# Attenuverting_LinExp_VCA-alt1.net
KiCad netlist of a schematic drawn in EAGLE
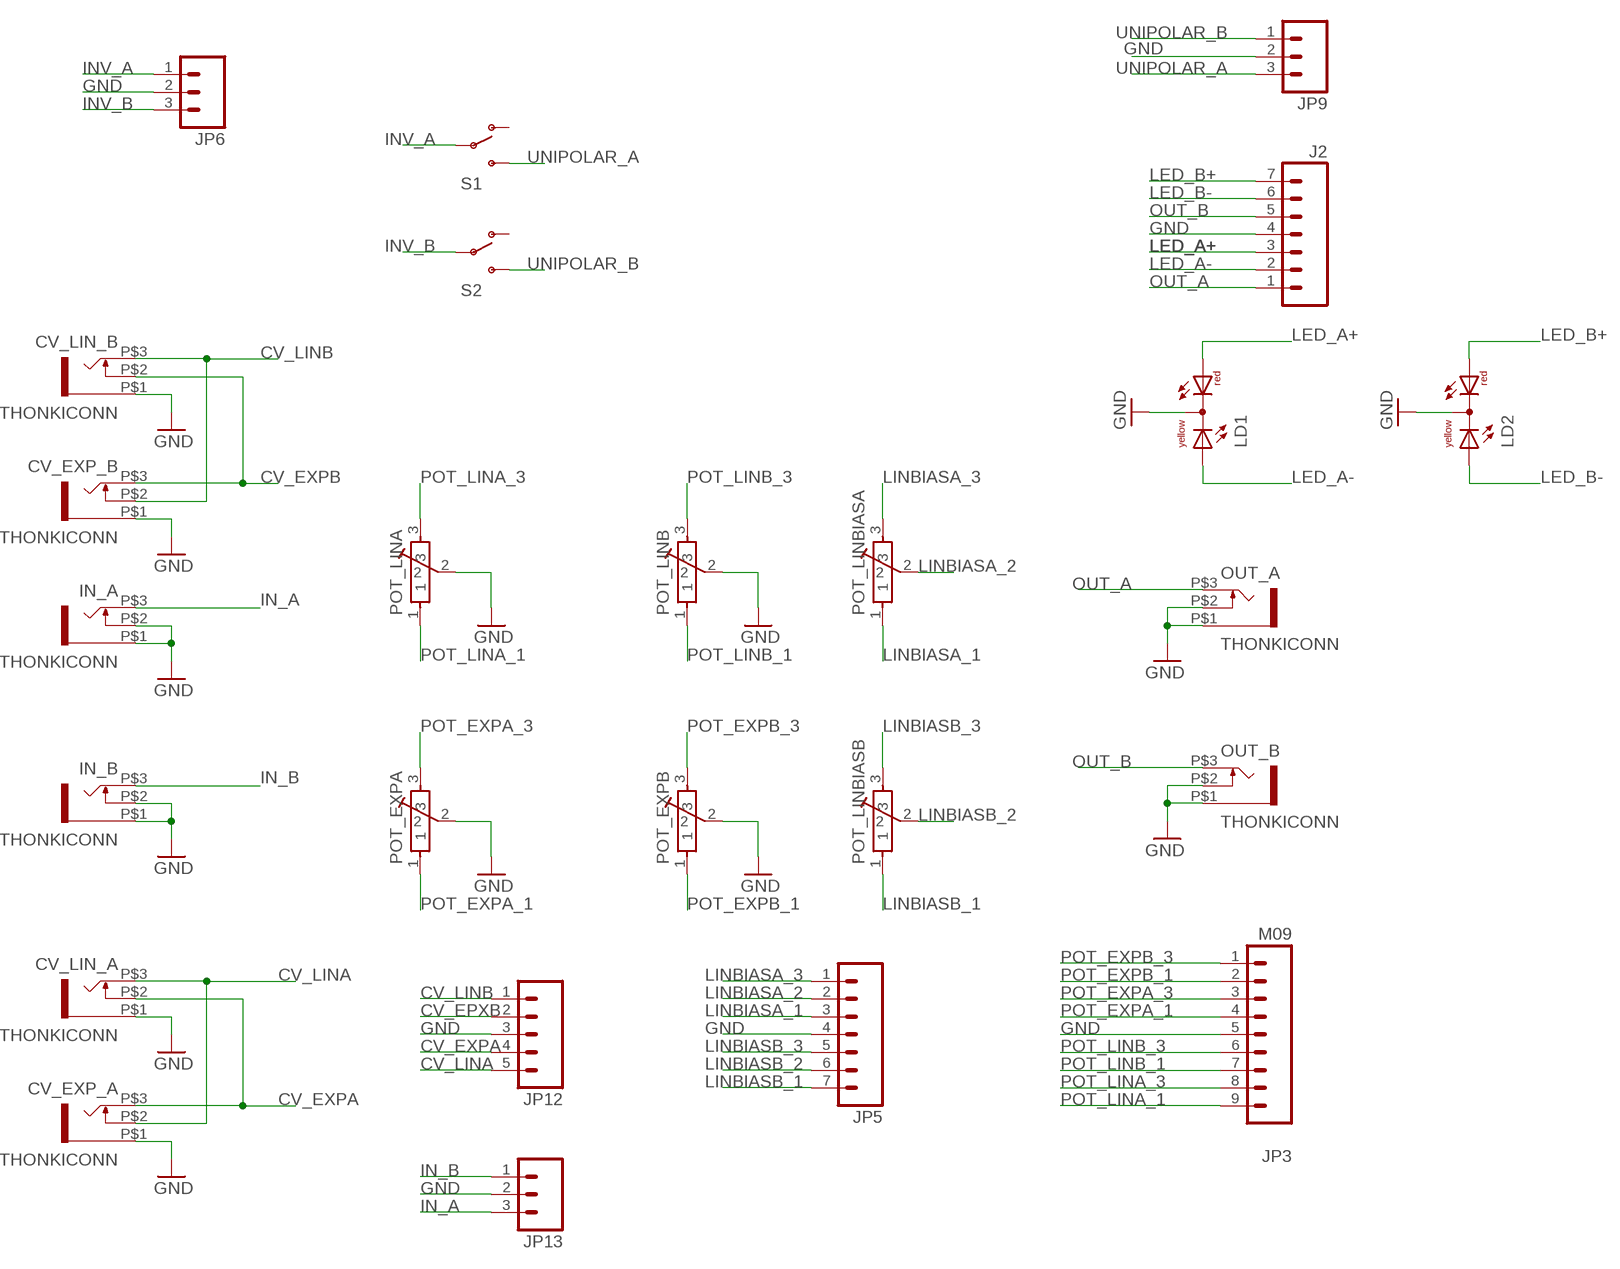
[diagram p0: schematic, sheet 1]
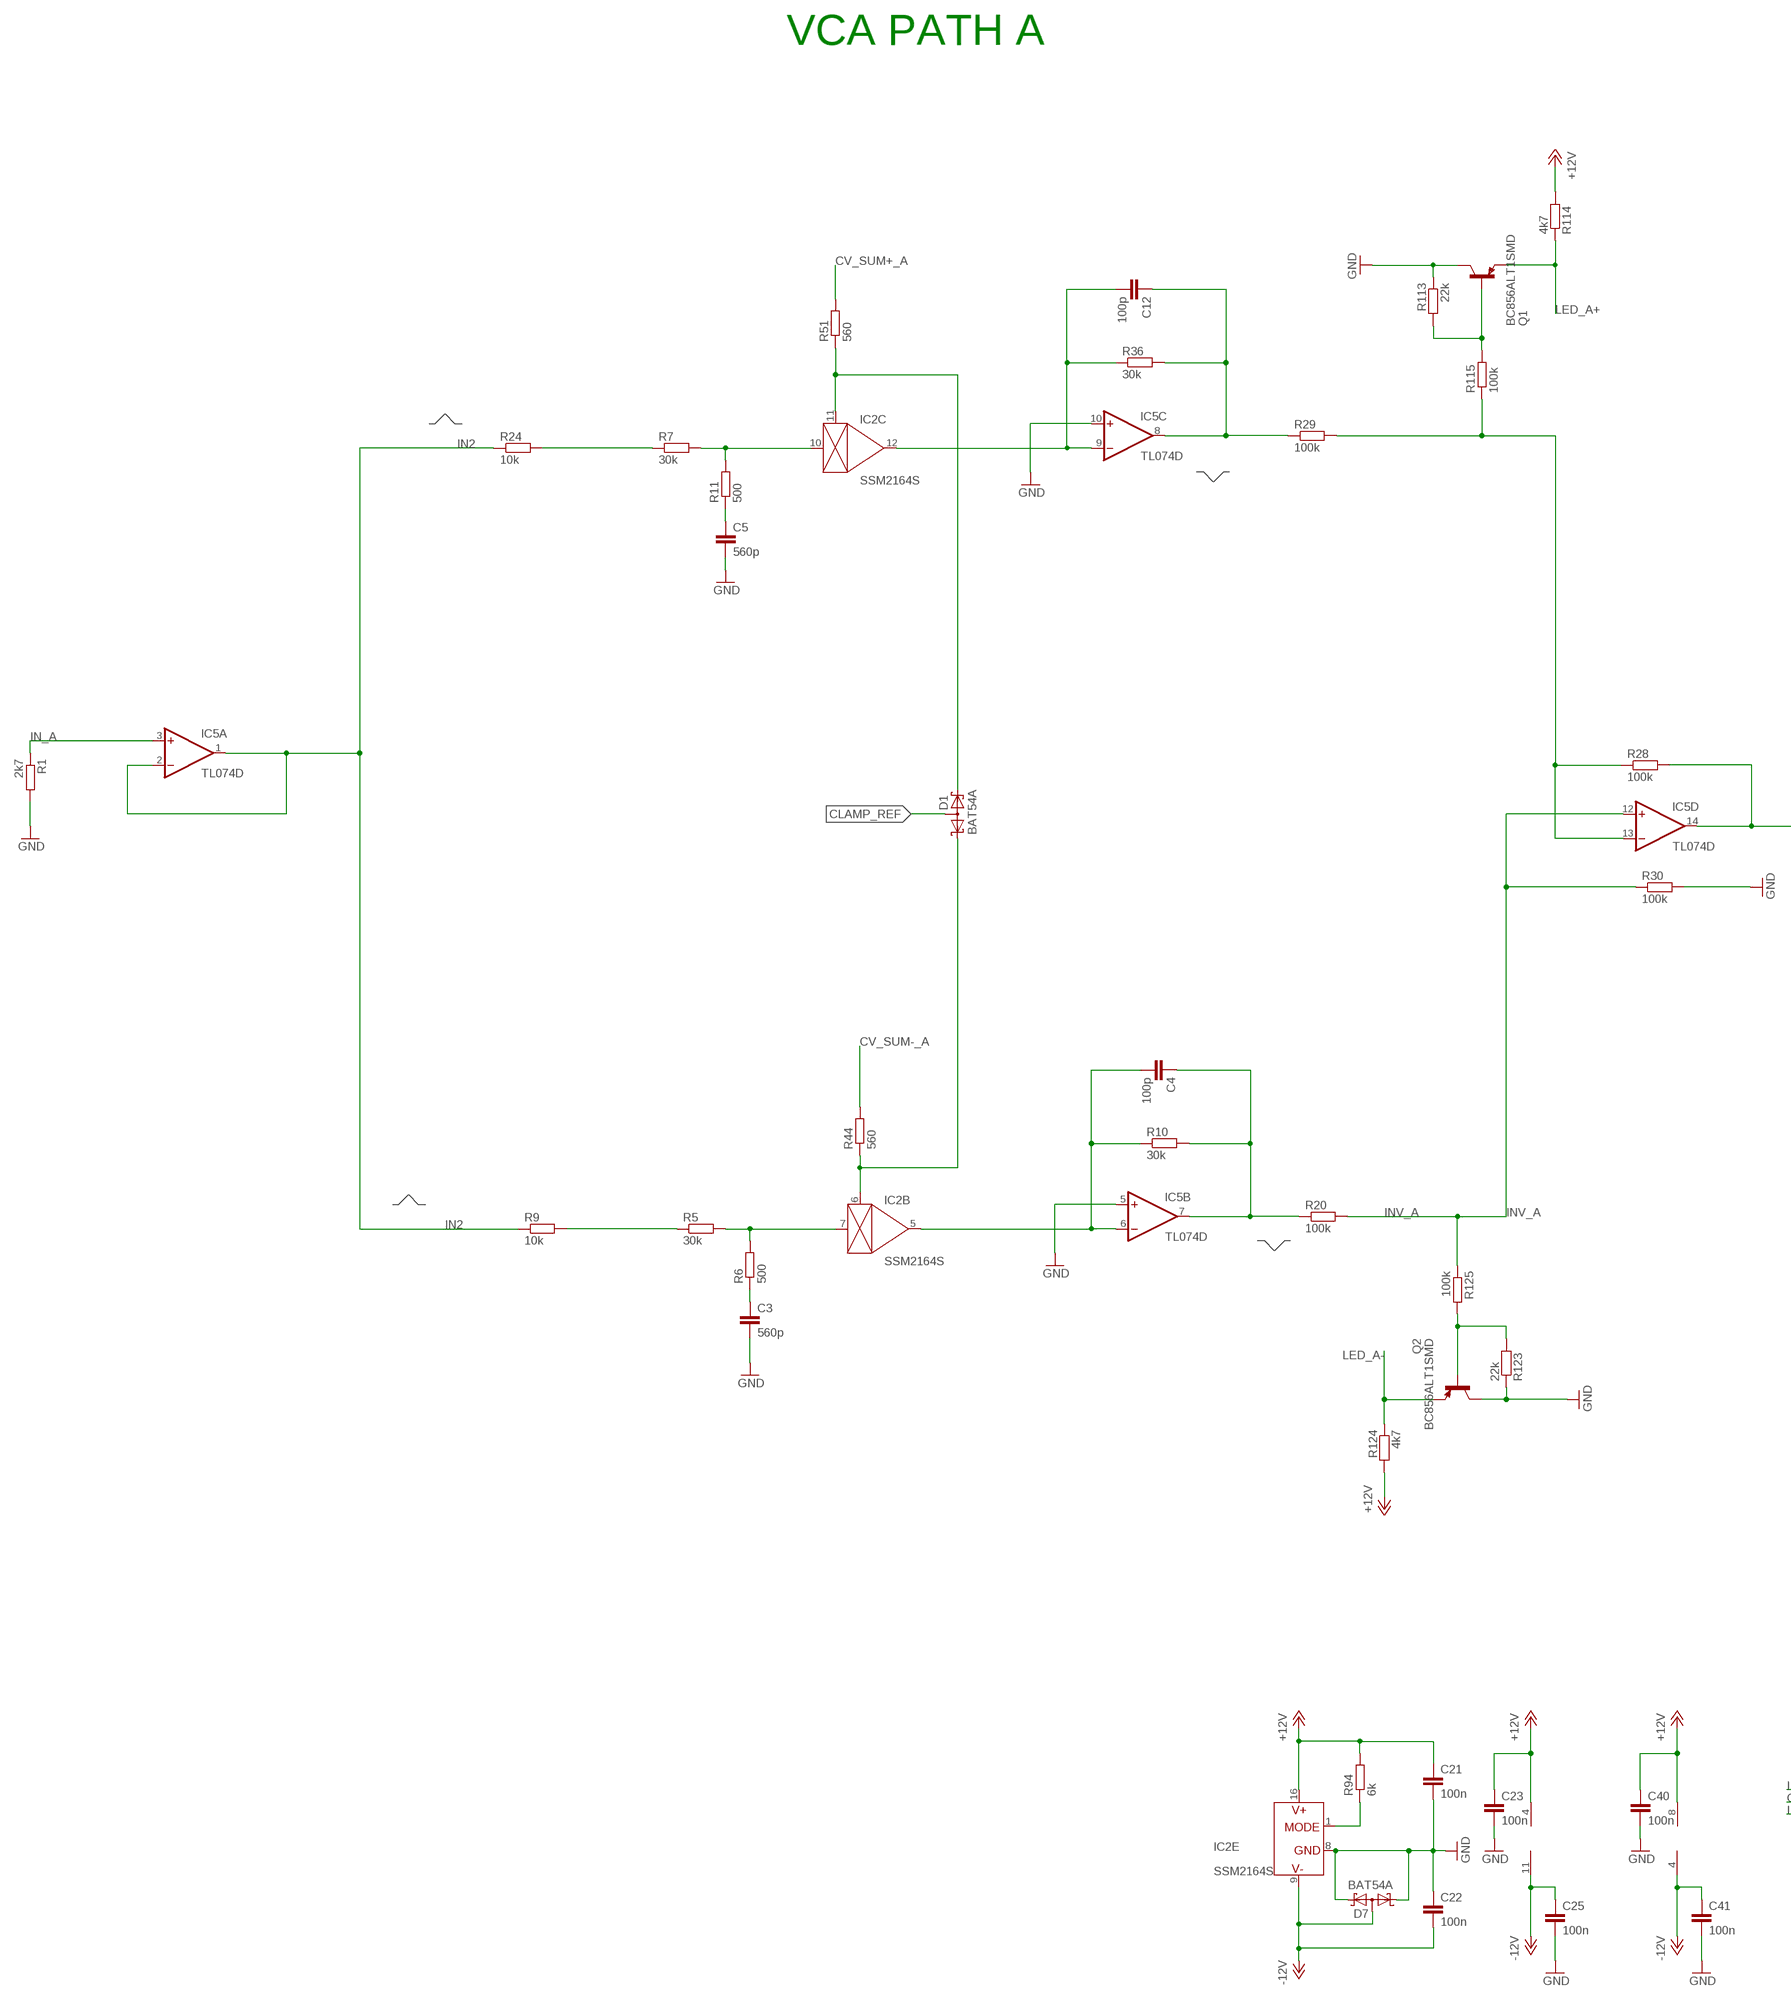
[diagram p1: schematic, sheet 2, part 1 of 2]
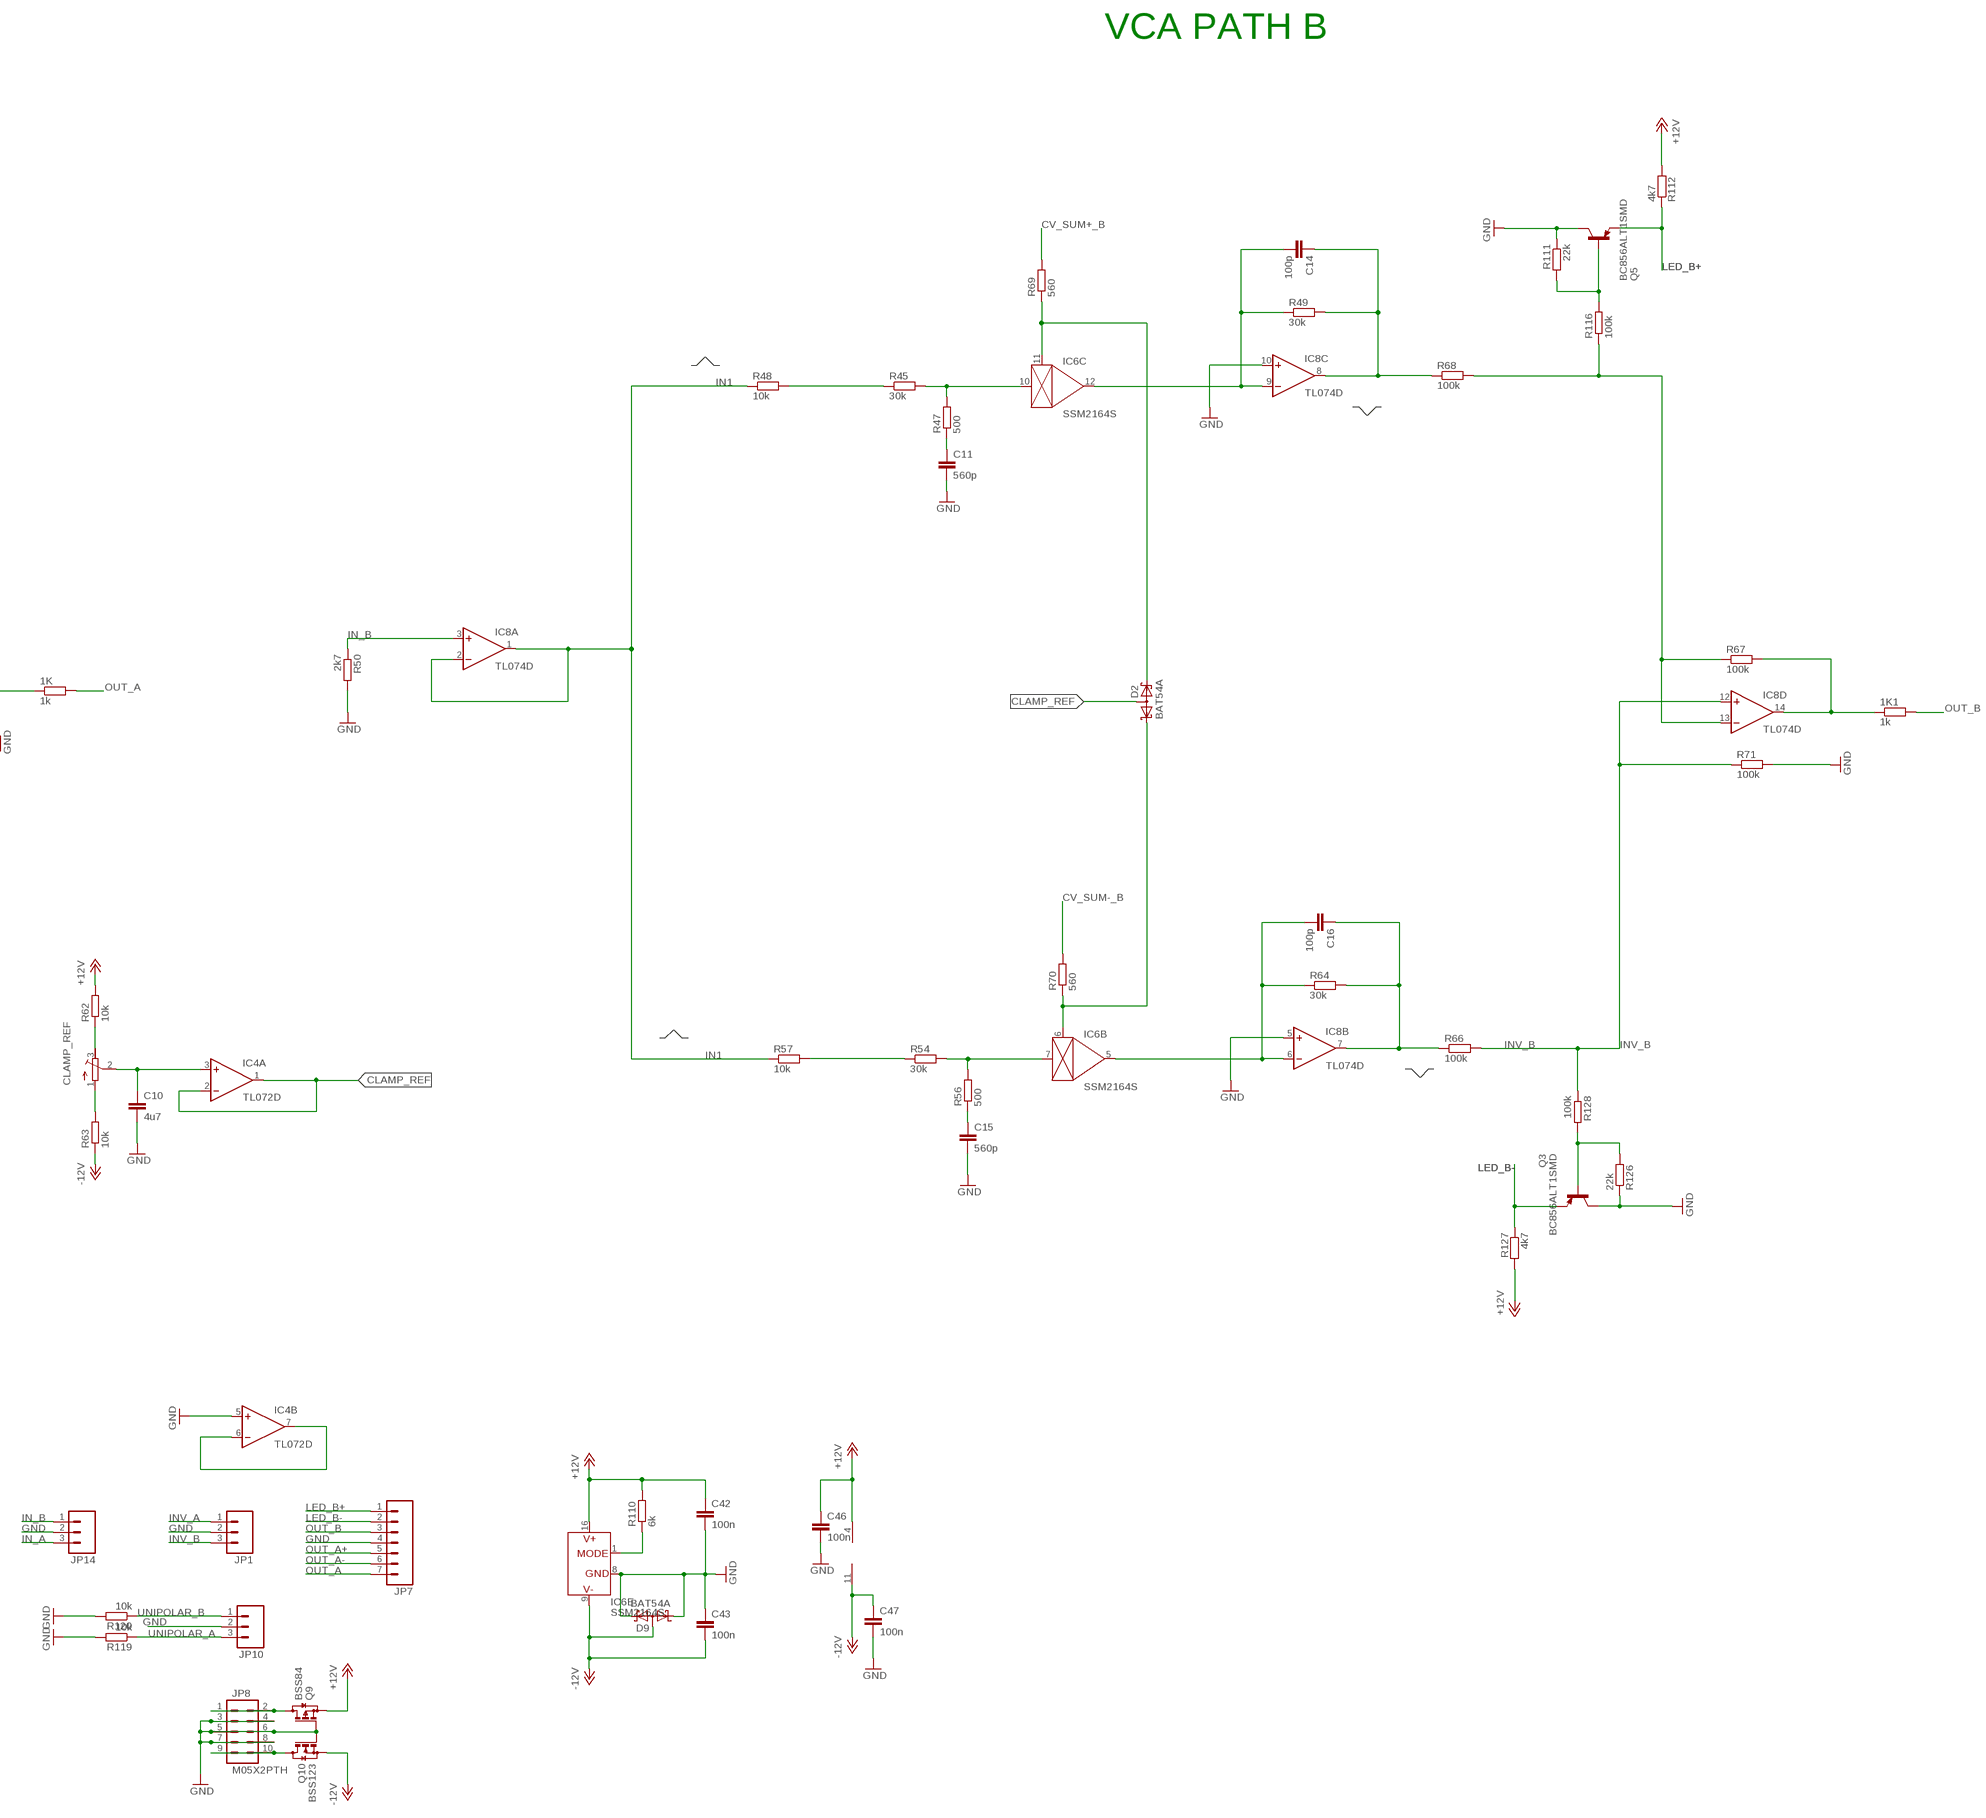
[diagram p2: schematic, sheet 2, part 2 of 2]
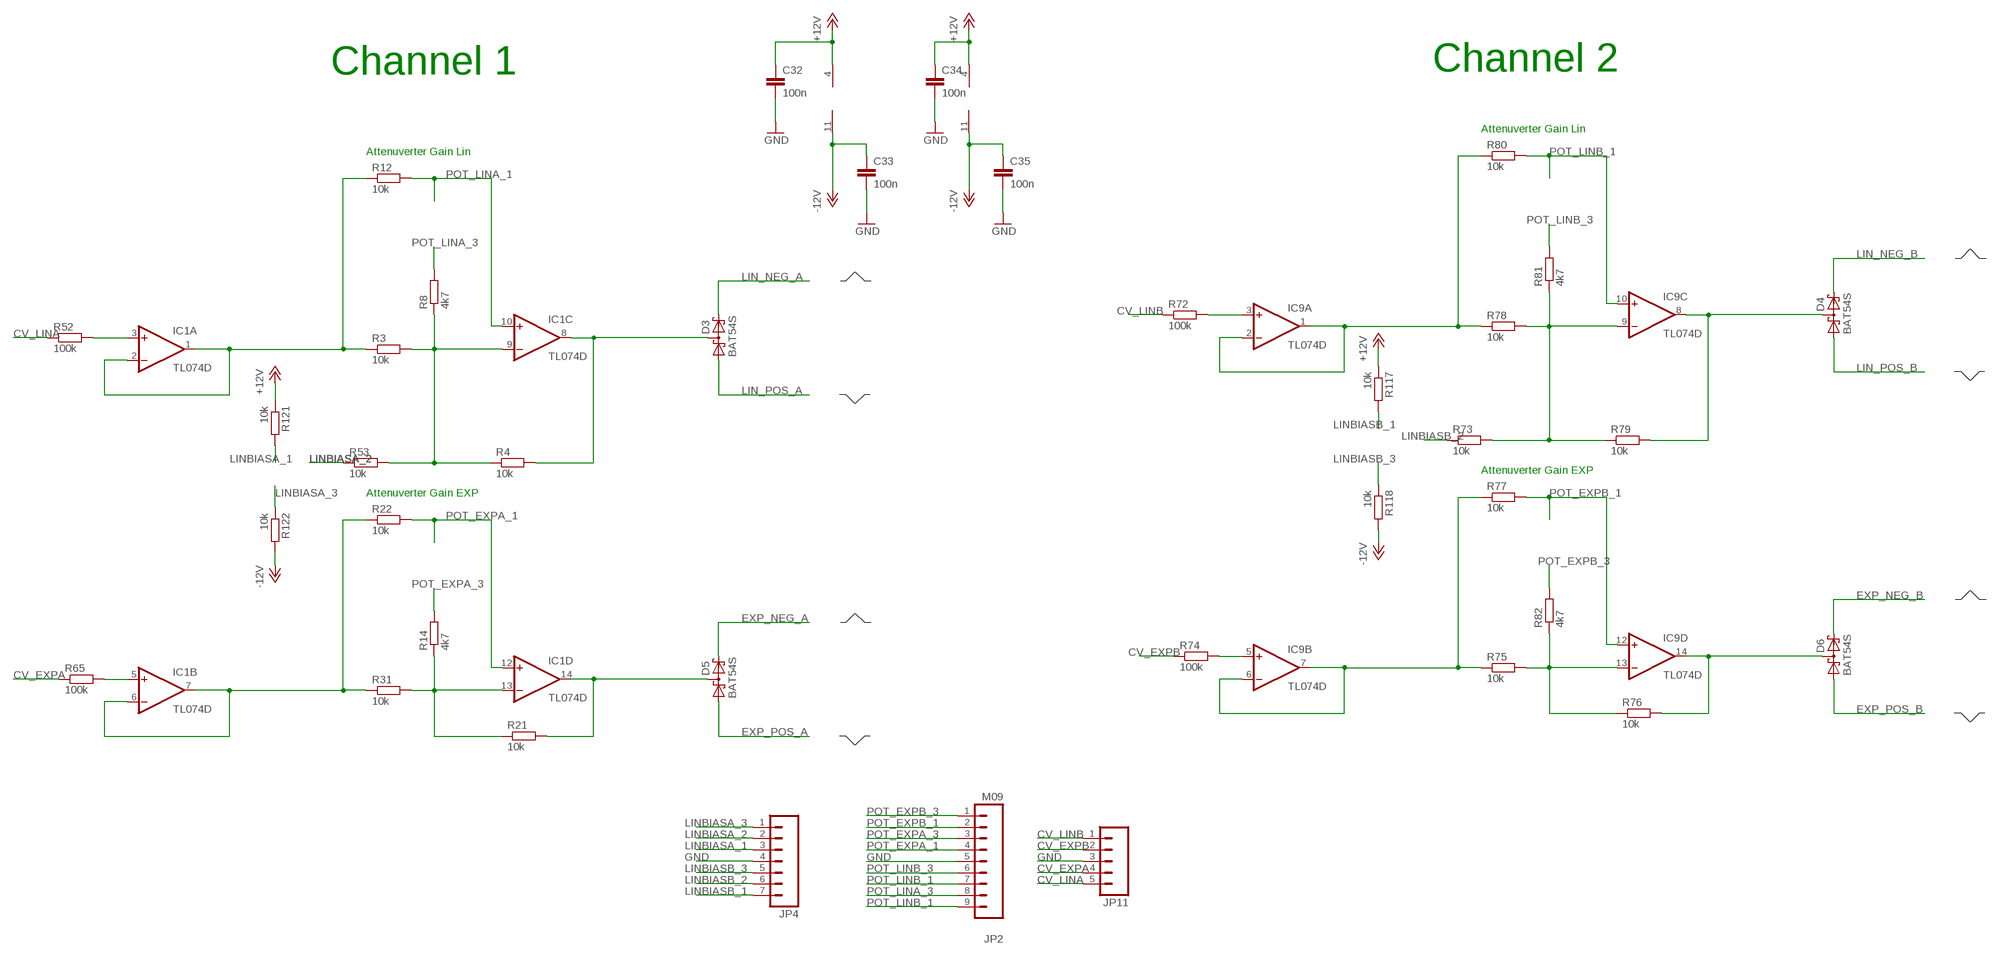
[diagram p3: schematic, sheet 3]
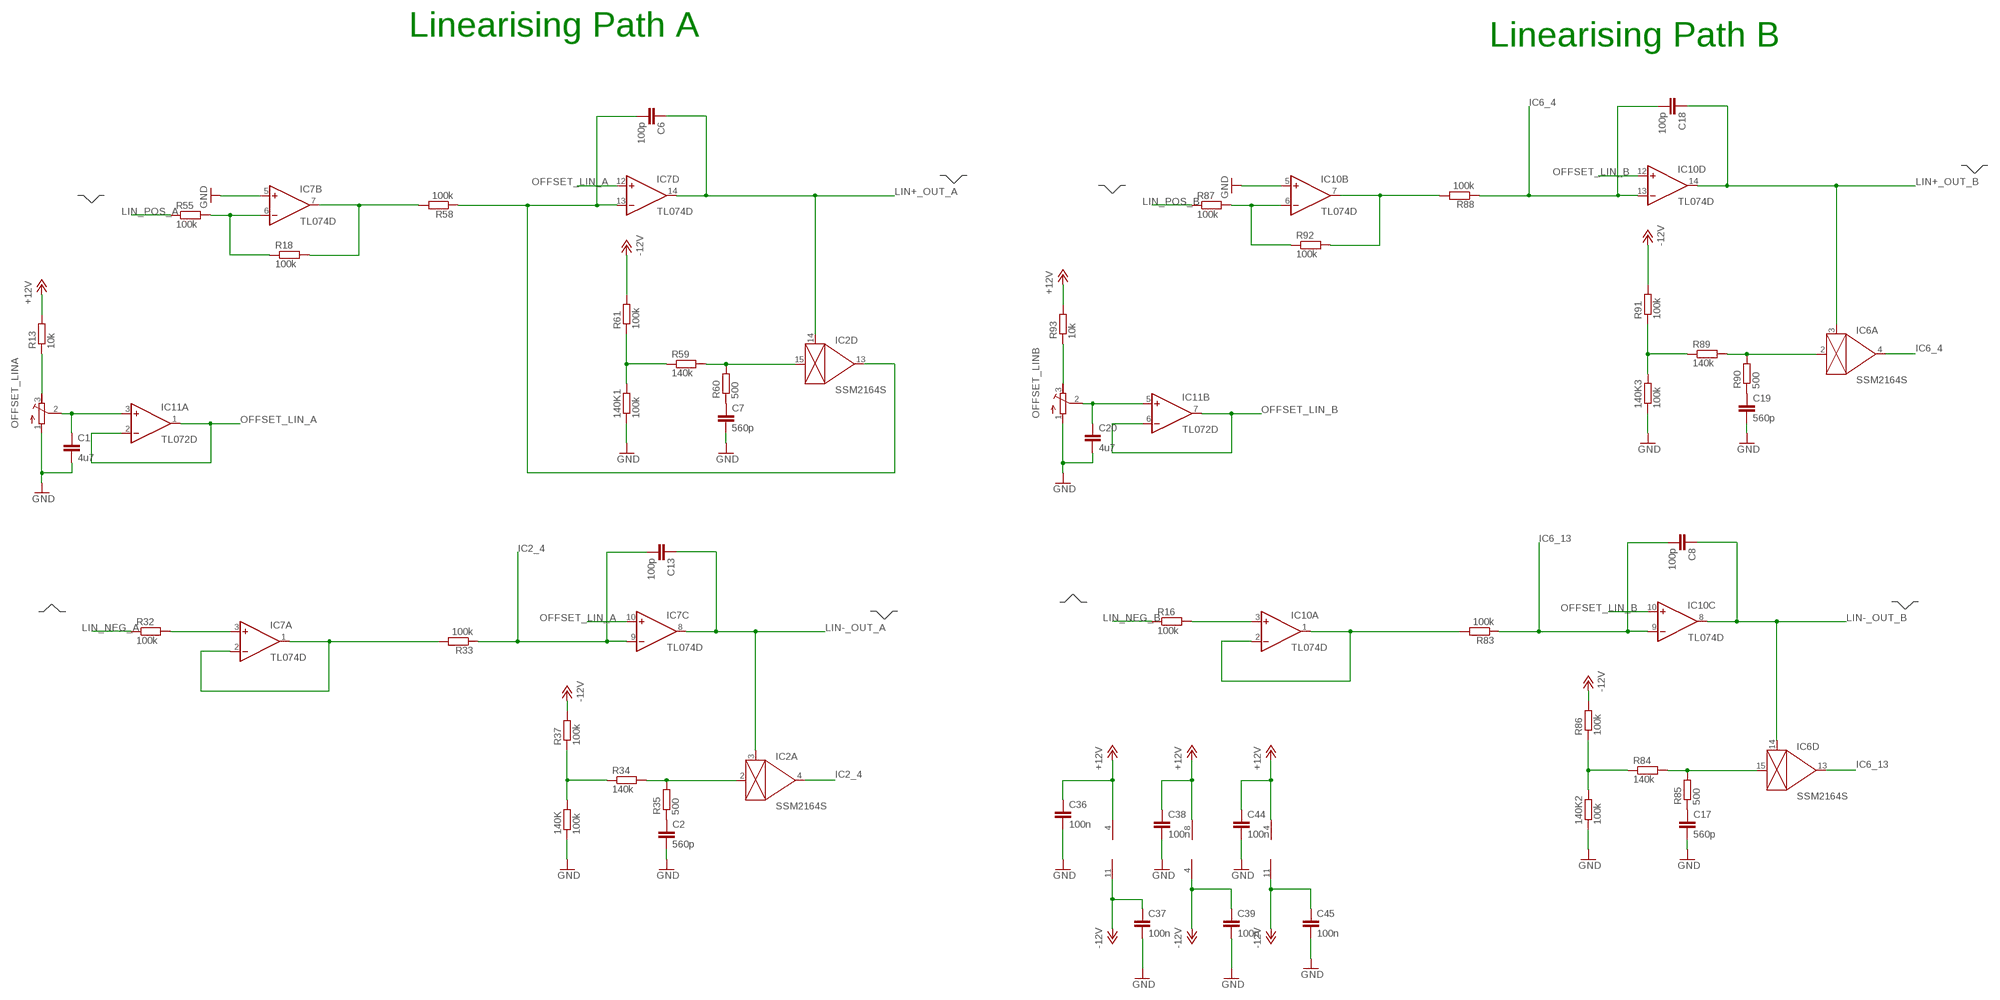
[diagram p4: schematic, sheet 4]
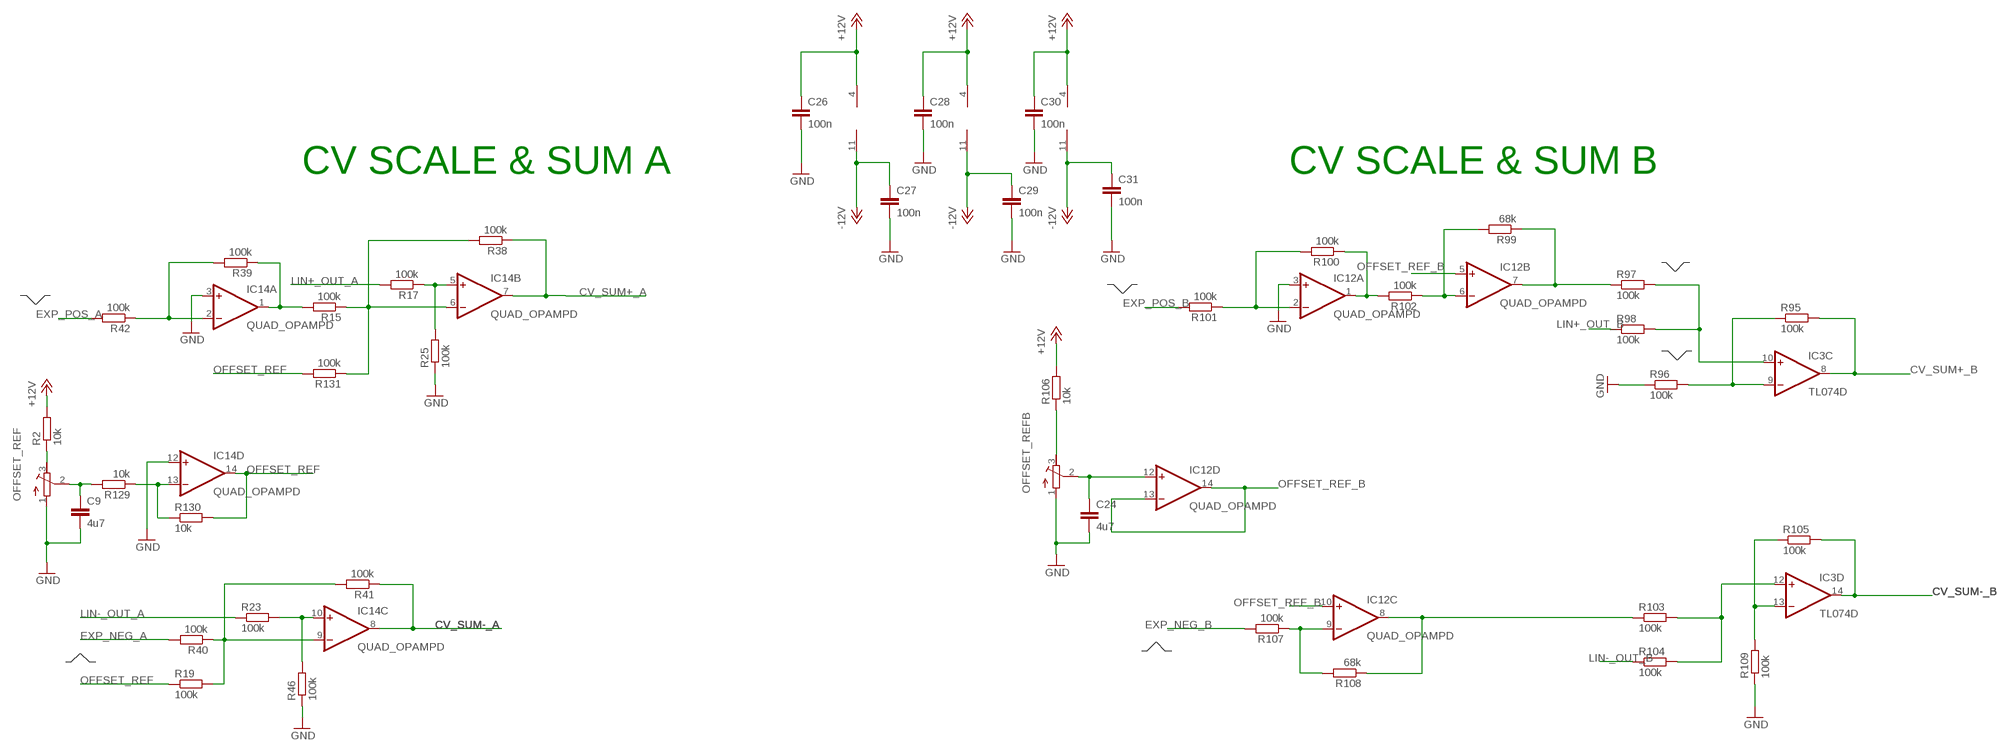
[diagram p5: schematic, sheet 5]

(export (version "E")
  (design (tool "Eeschema 10.0.6"))
  (components
    (comp (ref "1K")
      (value "1k")
      (footprint "eagle-import:0603")
      (fields (field (name "MF") "MULTICOMP") (field (name "MPN") "MC0063W06031160K"))
      (libsource (lib "eagle-import") (part "R-EU_0603"))
    )
    (comp (ref "1K1")
      (value "1k")
      (footprint "eagle-import:0603")
      (fields (field (name "MF") "MULTICOMP") (field (name "MPN") "MC0063W06031160K"))
      (libsource (lib "eagle-import") (part "R-EU_0603"))
    )
    (comp (ref "C3")
      (value "560p")
      (footprint "eagle-import:C0603K")
      (libsource (lib "eagle-import") (part "resistor_C-EUC0603K"))
    )
    (comp (ref "C4")
      (value "100p")
      (footprint "eagle-import:C0603K")
      (libsource (lib "eagle-import") (part "resistor_C-EUC0603K"))
    )
    (comp (ref "C5")
      (value "560p")
      (footprint "eagle-import:C0603K")
      (libsource (lib "eagle-import") (part "resistor_C-EUC0603K"))
    )
    (comp (ref "C10")
      (value "4u7")
      (footprint "eagle-import:C0603K")
      (libsource (lib "eagle-import") (part "resistor_C-EUC0603K"))
    )
    (comp (ref "C11")
      (value "560p")
      (footprint "eagle-import:C0603K")
      (libsource (lib "eagle-import") (part "resistor_C-EUC0603K"))
    )
    (comp (ref "C12")
      (value "100p")
      (footprint "eagle-import:C0603K")
      (libsource (lib "eagle-import") (part "resistor_C-EUC0603K"))
    )
    (comp (ref "C14")
      (value "100p")
      (footprint "eagle-import:C0603K")
      (libsource (lib "eagle-import") (part "resistor_C-EUC0603K"))
    )
    (comp (ref "C15")
      (value "560p")
      (footprint "eagle-import:C0603K")
      (libsource (lib "eagle-import") (part "resistor_C-EUC0603K"))
    )
    (comp (ref "C16")
      (value "100p")
      (footprint "eagle-import:C0603K")
      (libsource (lib "eagle-import") (part "resistor_C-EUC0603K"))
    )
    (comp (ref "C21")
      (value "100n")
      (footprint "eagle-import:C0603K")
      (libsource (lib "eagle-import") (part "C-EUC0603K"))
    )
    (comp (ref "C22")
      (value "100n")
      (footprint "eagle-import:C0603K")
      (libsource (lib "eagle-import") (part "C-EUC0603K"))
    )
    (comp (ref "C23")
      (value "100n")
      (footprint "eagle-import:C0603K")
      (libsource (lib "eagle-import") (part "C-EUC0603K"))
    )
    (comp (ref "C25")
      (value "100n")
      (footprint "eagle-import:C0603K")
      (libsource (lib "eagle-import") (part "C-EUC0603K"))
    )
    (comp (ref "C40")
      (value "100n")
      (footprint "eagle-import:C0603K")
      (libsource (lib "eagle-import") (part "C-EUC0603K"))
    )
    (comp (ref "C41")
      (value "100n")
      (footprint "eagle-import:C0603K")
      (libsource (lib "eagle-import") (part "C-EUC0603K"))
    )
    (comp (ref "C42")
      (value "100n")
      (footprint "eagle-import:C0603K")
      (libsource (lib "eagle-import") (part "C-EUC0603K"))
    )
    (comp (ref "C43")
      (value "100n")
      (footprint "eagle-import:C0603K")
      (libsource (lib "eagle-import") (part "C-EUC0603K"))
    )
    (comp (ref "C46")
      (value "100n")
      (footprint "eagle-import:C0603K")
      (libsource (lib "eagle-import") (part "C-EUC0603K"))
    )
    (comp (ref "C47")
      (value "100n")
      (footprint "eagle-import:C0603K")
      (libsource (lib "eagle-import") (part "C-EUC0603K"))
    )
    (comp (ref "CLAMP_REF")
      (value "R-TRIMM64W")
      (footprint "eagle-import:RTRIM64W")
      (libsource (lib "eagle-import") (part "R-TRIMM64W"))
    )
    (comp (ref "D1")
      (value "BAT54A")
      (footprint "eagle-import:SOT23")
      (libsource (lib "eagle-import") (part "BAT54A"))
    )
    (comp (ref "D2")
      (value "BAT54A")
      (footprint "eagle-import:SOT23")
      (libsource (lib "eagle-import") (part "BAT54A"))
    )
    (comp (ref "D7")
      (value "BAT54A")
      (footprint "eagle-import:SOT23")
      (libsource (lib "eagle-import") (part "BAT54A"))
    )
    (comp (ref "D9")
      (value "BAT54A")
      (footprint "eagle-import:SOT23")
      (libsource (lib "eagle-import") (part "BAT54A"))
    )
    (comp (ref "IC2")
      (value "SSM2164S")
      (footprint "eagle-import:SOIC16N")
      (fields (field (name "OC_FARNELL") "unknown"))
      (libsource (lib "eagle-import") (part "SSM2164S"))
    )
    (comp (ref "IC4")
      (value "TL072D")
      (footprint "eagle-import:SO08")
      (libsource (lib "eagle-import") (part "TL072D"))
    )
    (comp (ref "IC5")
      (value "TL074D")
      (footprint "eagle-import:SO14")
      (fields (field (name "OC_FARNELL") "unknown"))
      (libsource (lib "eagle-import") (part "TL074D"))
    )
    (comp (ref "IC6")
      (value "SSM2164S")
      (footprint "eagle-import:SOIC16N")
      (fields (field (name "OC_FARNELL") "unknown"))
      (libsource (lib "eagle-import") (part "SSM2164S"))
    )
    (comp (ref "IC8")
      (value "TL074D")
      (footprint "eagle-import:SO14")
      (fields (field (name "OC_FARNELL") "unknown"))
      (libsource (lib "eagle-import") (part "TL074D"))
    )
    (comp (ref "JP1")
      (value "M03PTH")
      (footprint "eagle-import:1X03")
      (libsource (lib "eagle-import") (part "M03PTH"))
    )
    (comp (ref "JP7")
      (value "M07")
      (footprint "eagle-import:1X07")
      (libsource (lib "eagle-import") (part "M07"))
    )
    (comp (ref "JP8")
      (value "M05X2PTH")
      (footprint "eagle-import:AVR_ICSP")
      (libsource (lib "eagle-import") (part "M05X2PTH"))
    )
    (comp (ref "JP10")
      (value "M03PTH")
      (footprint "eagle-import:1X03")
      (libsource (lib "eagle-import") (part "M03PTH"))
    )
    (comp (ref "JP14")
      (value "M03PTH")
      (footprint "eagle-import:1X03")
      (libsource (lib "eagle-import") (part "M03PTH"))
    )
    (comp (ref "Q1")
      (value "BC856ALT1SMD")
      (footprint "eagle-import:SOT23-BEC")
      (libsource (lib "eagle-import") (part "BC856SMDALT1"))
    )
    (comp (ref "Q2")
      (value "BC856ALT1SMD")
      (footprint "eagle-import:SOT23-BEC")
      (libsource (lib "eagle-import") (part "BC856SMDALT1"))
    )
    (comp (ref "Q3")
      (value "BC856ALT1SMD")
      (footprint "eagle-import:SOT23-BEC")
      (libsource (lib "eagle-import") (part "BC856SMDALT1"))
    )
    (comp (ref "Q5")
      (value "BC856ALT1SMD")
      (footprint "eagle-import:SOT23-BEC")
      (libsource (lib "eagle-import") (part "BC856SMDALT1"))
    )
    (comp (ref "Q9")
      (value "BSS84")
      (footprint "eagle-import:SOT23")
      (libsource (lib "eagle-import") (part "BSS84"))
    )
    (comp (ref "Q10")
      (value "BSS123")
      (footprint "eagle-import:SOT23")
      (libsource (lib "eagle-import") (part "BSS123"))
    )
    (comp (ref "R1")
      (value "2k7")
      (footprint "eagle-import:0603")
      (libsource (lib "eagle-import") (part "R-EU_0603"))
    )
    (comp (ref "R5")
      (value "30k")
      (footprint "eagle-import:0603")
      (libsource (lib "eagle-import") (part "R-EU_0603"))
    )
    (comp (ref "R6")
      (value "500")
      (footprint "eagle-import:0603")
      (libsource (lib "eagle-import") (part "R-EU_0603"))
    )
    (comp (ref "R7")
      (value "30k")
      (footprint "eagle-import:0603")
      (libsource (lib "eagle-import") (part "R-EU_0603"))
    )
    (comp (ref "R9")
      (value "10k")
      (footprint "eagle-import:0603")
      (libsource (lib "eagle-import") (part "R-EU_0603"))
    )
    (comp (ref "R10")
      (value "30k")
      (footprint "eagle-import:0603")
      (libsource (lib "eagle-import") (part "R-EU_0603"))
    )
    (comp (ref "R11")
      (value "500")
      (footprint "eagle-import:0603")
      (libsource (lib "eagle-import") (part "R-EU_0603"))
    )
    (comp (ref "R20")
      (value "100k")
      (footprint "eagle-import:0603")
      (libsource (lib "eagle-import") (part "R-EU_0603"))
    )
    (comp (ref "R24")
      (value "10k")
      (footprint "eagle-import:0603")
      (libsource (lib "eagle-import") (part "R-EU_0603"))
    )
    (comp (ref "R28")
      (value "100k")
      (footprint "eagle-import:0603")
      (libsource (lib "eagle-import") (part "R-EU_0603"))
    )
    (comp (ref "R29")
      (value "100k")
      (footprint "eagle-import:0603")
      (libsource (lib "eagle-import") (part "R-EU_0603"))
    )
    (comp (ref "R30")
      (value "100k")
      (footprint "eagle-import:0603")
      (libsource (lib "eagle-import") (part "R-EU_0603"))
    )
    (comp (ref "R36")
      (value "30k")
      (footprint "eagle-import:0603")
      (libsource (lib "eagle-import") (part "R-EU_0603"))
    )
    (comp (ref "R44")
      (value "560")
      (footprint "eagle-import:0603")
      (libsource (lib "eagle-import") (part "R-EU_0603"))
    )
    (comp (ref "R45")
      (value "30k")
      (footprint "eagle-import:0603")
      (libsource (lib "eagle-import") (part "R-EU_0603"))
    )
    (comp (ref "R47")
      (value "500")
      (footprint "eagle-import:0603")
      (libsource (lib "eagle-import") (part "R-EU_0603"))
    )
    (comp (ref "R48")
      (value "10k")
      (footprint "eagle-import:0603")
      (libsource (lib "eagle-import") (part "R-EU_0603"))
    )
    (comp (ref "R49")
      (value "30k")
      (footprint "eagle-import:0603")
      (libsource (lib "eagle-import") (part "R-EU_0603"))
    )
    (comp (ref "R50")
      (value "2k7")
      (footprint "eagle-import:0603")
      (libsource (lib "eagle-import") (part "R-EU_0603"))
    )
    (comp (ref "R51")
      (value "560")
      (footprint "eagle-import:0603")
      (libsource (lib "eagle-import") (part "R-EU_0603"))
    )
    (comp (ref "R54")
      (value "30k")
      (footprint "eagle-import:0603")
      (libsource (lib "eagle-import") (part "R-EU_0603"))
    )
    (comp (ref "R56")
      (value "500")
      (footprint "eagle-import:0603")
      (libsource (lib "eagle-import") (part "R-EU_0603"))
    )
    (comp (ref "R57")
      (value "10k")
      (footprint "eagle-import:0603")
      (libsource (lib "eagle-import") (part "R-EU_0603"))
    )
    (comp (ref "R62")
      (value "10k")
      (footprint "eagle-import:0603")
      (libsource (lib "eagle-import") (part "R-EU_0603"))
    )
    (comp (ref "R63")
      (value "10k")
      (footprint "eagle-import:0603")
      (libsource (lib "eagle-import") (part "R-EU_0603"))
    )
    (comp (ref "R64")
      (value "30k")
      (footprint "eagle-import:0603")
      (libsource (lib "eagle-import") (part "R-EU_0603"))
    )
    (comp (ref "R66")
      (value "100k")
      (footprint "eagle-import:0603")
      (libsource (lib "eagle-import") (part "R-EU_0603"))
    )
    (comp (ref "R67")
      (value "100k")
      (footprint "eagle-import:0603")
      (libsource (lib "eagle-import") (part "R-EU_0603"))
    )
    (comp (ref "R68")
      (value "100k")
      (footprint "eagle-import:0603")
      (libsource (lib "eagle-import") (part "R-EU_0603"))
    )
    (comp (ref "R69")
      (value "560")
      (footprint "eagle-import:0603")
      (libsource (lib "eagle-import") (part "R-EU_0603"))
    )
    (comp (ref "R70")
      (value "560")
      (footprint "eagle-import:0603")
      (libsource (lib "eagle-import") (part "R-EU_0603"))
    )
    (comp (ref "R71")
      (value "100k")
      (footprint "eagle-import:0603")
      (libsource (lib "eagle-import") (part "R-EU_0603"))
    )
    (comp (ref "R94")
      (value "6k")
      (footprint "eagle-import:0603")
      (libsource (lib "eagle-import") (part "R-EU_0603"))
    )
    (comp (ref "R110")
      (value "6k")
      (footprint "eagle-import:0603")
      (libsource (lib "eagle-import") (part "R-EU_0603"))
    )
    (comp (ref "R111")
      (value "22k")
      (footprint "eagle-import:0603")
      (libsource (lib "eagle-import") (part "R-EU_0603"))
    )
    (comp (ref "R112")
      (value "4k7")
      (footprint "eagle-import:0603")
      (libsource (lib "eagle-import") (part "R-EU_0603"))
    )
    (comp (ref "R113")
      (value "22k")
      (footprint "eagle-import:0603")
      (libsource (lib "eagle-import") (part "R-EU_0603"))
    )
    (comp (ref "R114")
      (value "4k7")
      (footprint "eagle-import:0603")
      (libsource (lib "eagle-import") (part "R-EU_0603"))
    )
    (comp (ref "R115")
      (value "100k")
      (footprint "eagle-import:0603")
      (libsource (lib "eagle-import") (part "R-EU_0603"))
    )
    (comp (ref "R116")
      (value "100k")
      (footprint "eagle-import:0603")
      (libsource (lib "eagle-import") (part "R-EU_0603"))
    )
    (comp (ref "R119")
      (value "10k")
      (footprint "eagle-import:0603")
      (libsource (lib "eagle-import") (part "R-EU_0603"))
    )
    (comp (ref "R120")
      (value "10k")
      (footprint "eagle-import:0603")
      (libsource (lib "eagle-import") (part "R-EU_0603"))
    )
    (comp (ref "R123")
      (value "22k")
      (footprint "eagle-import:0603")
      (libsource (lib "eagle-import") (part "R-EU_0603"))
    )
    (comp (ref "R124")
      (value "4k7")
      (footprint "eagle-import:0603")
      (libsource (lib "eagle-import") (part "R-EU_0603"))
    )
    (comp (ref "R125")
      (value "100k")
      (footprint "eagle-import:0603")
      (libsource (lib "eagle-import") (part "R-EU_0603"))
    )
    (comp (ref "R126")
      (value "22k")
      (footprint "eagle-import:0603")
      (libsource (lib "eagle-import") (part "R-EU_0603"))
    )
    (comp (ref "R127")
      (value "4k7")
      (footprint "eagle-import:0603")
      (libsource (lib "eagle-import") (part "R-EU_0603"))
    )
    (comp (ref "R128")
      (value "100k")
      (footprint "eagle-import:0603")
      (libsource (lib "eagle-import") (part "R-EU_0603"))
    )
    (comp (ref "C32")
      (value "100n")
      (footprint "eagle-import:C0603K")
      (libsource (lib "eagle-import") (part "C-EUC0603K"))
    )
    (comp (ref "C33")
      (value "100n")
      (footprint "eagle-import:C0603K")
      (libsource (lib "eagle-import") (part "C-EUC0603K"))
    )
    (comp (ref "C34")
      (value "100n")
      (footprint "eagle-import:C0603K")
      (libsource (lib "eagle-import") (part "C-EUC0603K"))
    )
    (comp (ref "C35")
      (value "100n")
      (footprint "eagle-import:C0603K")
      (libsource (lib "eagle-import") (part "C-EUC0603K"))
    )
    (comp (ref "D3")
      (value "BAT54S")
      (footprint "eagle-import:SOT23")
      (libsource (lib "eagle-import") (part "BAT54S"))
    )
    (comp (ref "D4")
      (value "BAT54S")
      (footprint "eagle-import:SOT23")
      (libsource (lib "eagle-import") (part "BAT54S"))
    )
    (comp (ref "D5")
      (value "BAT54S")
      (footprint "eagle-import:SOT23")
      (libsource (lib "eagle-import") (part "BAT54S"))
    )
    (comp (ref "D6")
      (value "BAT54S")
      (footprint "eagle-import:SOT23")
      (libsource (lib "eagle-import") (part "BAT54S"))
    )
    (comp (ref "IC1")
      (value "TL074D")
      (footprint "eagle-import:SO14")
      (fields (field (name "OC_FARNELL") "unknown"))
      (libsource (lib "eagle-import") (part "TL074D"))
    )
    (comp (ref "IC9")
      (value "TL074D")
      (footprint "eagle-import:SO14")
      (fields (field (name "OC_FARNELL") "unknown"))
      (libsource (lib "eagle-import") (part "TL074D"))
    )
    (comp (ref "JP2")
      (value "M09")
      (footprint "eagle-import:1X09")
      (libsource (lib "eagle-import") (part "M09"))
    )
    (comp (ref "JP4")
      (value "M07")
      (footprint "eagle-import:1X07")
      (libsource (lib "eagle-import") (part "M07"))
    )
    (comp (ref "JP11")
      (value "M05PTH")
      (footprint "eagle-import:1X05")
      (libsource (lib "eagle-import") (part "M05PTH"))
    )
    (comp (ref "R3")
      (value "10k")
      (footprint "eagle-import:0603")
      (libsource (lib "eagle-import") (part "R-EU_0603"))
    )
    (comp (ref "R4")
      (value "10k")
      (footprint "eagle-import:0603")
      (libsource (lib "eagle-import") (part "R-EU_0603"))
    )
    (comp (ref "R8")
      (value "4k7")
      (footprint "eagle-import:0603")
      (libsource (lib "eagle-import") (part "R-EU_0603"))
    )
    (comp (ref "R12")
      (value "10k")
      (footprint "eagle-import:0603")
      (libsource (lib "eagle-import") (part "R-EU_0603"))
    )
    (comp (ref "R14")
      (value "4k7")
      (footprint "eagle-import:0603")
      (libsource (lib "eagle-import") (part "R-EU_0603"))
    )
    (comp (ref "R21")
      (value "10k")
      (footprint "eagle-import:0603")
      (libsource (lib "eagle-import") (part "R-EU_0603"))
    )
    (comp (ref "R22")
      (value "10k")
      (footprint "eagle-import:0603")
      (libsource (lib "eagle-import") (part "R-EU_0603"))
    )
    (comp (ref "R31")
      (value "10k")
      (footprint "eagle-import:0603")
      (libsource (lib "eagle-import") (part "R-EU_0603"))
    )
    (comp (ref "R52")
      (value "100k")
      (footprint "eagle-import:0603")
      (libsource (lib "eagle-import") (part "R-EU_0603"))
    )
    (comp (ref "R53")
      (value "10k")
      (footprint "eagle-import:0603")
      (libsource (lib "eagle-import") (part "R-EU_0603"))
    )
    (comp (ref "R65")
      (value "100k")
      (footprint "eagle-import:0603")
      (libsource (lib "eagle-import") (part "R-EU_0603"))
    )
    (comp (ref "R72")
      (value "100k")
      (footprint "eagle-import:0603")
      (libsource (lib "eagle-import") (part "R-EU_0603"))
    )
    (comp (ref "R73")
      (value "10k")
      (footprint "eagle-import:0603")
      (libsource (lib "eagle-import") (part "R-EU_0603"))
    )
    (comp (ref "R74")
      (value "100k")
      (footprint "eagle-import:0603")
      (libsource (lib "eagle-import") (part "R-EU_0603"))
    )
    (comp (ref "R75")
      (value "10k")
      (footprint "eagle-import:0603")
      (libsource (lib "eagle-import") (part "R-EU_0603"))
    )
    (comp (ref "R76")
      (value "10k")
      (footprint "eagle-import:0603")
      (libsource (lib "eagle-import") (part "R-EU_0603"))
    )
    (comp (ref "R77")
      (value "10k")
      (footprint "eagle-import:0603")
      (libsource (lib "eagle-import") (part "R-EU_0603"))
    )
    (comp (ref "R78")
      (value "10k")
      (footprint "eagle-import:0603")
      (libsource (lib "eagle-import") (part "R-EU_0603"))
    )
    (comp (ref "R79")
      (value "10k")
      (footprint "eagle-import:0603")
      (libsource (lib "eagle-import") (part "R-EU_0603"))
    )
    (comp (ref "R80")
      (value "10k")
      (footprint "eagle-import:0603")
      (libsource (lib "eagle-import") (part "R-EU_0603"))
    )
    (comp (ref "R81")
      (value "4k7")
      (footprint "eagle-import:0603")
      (libsource (lib "eagle-import") (part "R-EU_0603"))
    )
    (comp (ref "R82")
      (value "4k7")
      (footprint "eagle-import:0603")
      (libsource (lib "eagle-import") (part "R-EU_0603"))
    )
    (comp (ref "R117")
      (value "10k")
      (footprint "eagle-import:0603")
      (libsource (lib "eagle-import") (part "R-EU_0603"))
    )
    (comp (ref "R118")
      (value "10k")
      (footprint "eagle-import:0603")
      (libsource (lib "eagle-import") (part "R-EU_0603"))
    )
    (comp (ref "R121")
      (value "10k")
      (footprint "eagle-import:0603")
      (libsource (lib "eagle-import") (part "R-EU_0603"))
    )
    (comp (ref "R122")
      (value "10k")
      (footprint "eagle-import:0603")
      (libsource (lib "eagle-import") (part "R-EU_0603"))
    )
    (comp (ref "CV_EXP_A")
      (value "THONKICONN")
      (footprint "eagle-import:THONKICONN")
      (libsource (lib "eagle-import") (part "THONKICONN"))
    )
    (comp (ref "CV_EXP_B")
      (value "THONKICONN")
      (footprint "eagle-import:THONKICONN")
      (libsource (lib "eagle-import") (part "THONKICONN"))
    )
    (comp (ref "CV_LIN_A")
      (value "THONKICONN")
      (footprint "eagle-import:THONKICONN")
      (libsource (lib "eagle-import") (part "THONKICONN"))
    )
    (comp (ref "CV_LIN_B")
      (value "THONKICONN")
      (footprint "eagle-import:THONKICONN")
      (libsource (lib "eagle-import") (part "THONKICONN"))
    )
    (comp (ref "IN_A")
      (value "THONKICONN")
      (footprint "eagle-import:THONKICONN")
      (libsource (lib "eagle-import") (part "THONKICONN"))
    )
    (comp (ref "IN_B")
      (value "THONKICONN")
      (footprint "eagle-import:THONKICONN")
      (libsource (lib "eagle-import") (part "THONKICONN"))
    )
    (comp (ref "J2")
      (value "M07")
      (footprint "eagle-import:1X07")
      (libsource (lib "eagle-import") (part "M07"))
    )
    (comp (ref "JP3")
      (value "M09")
      (footprint "eagle-import:1X09")
      (libsource (lib "eagle-import") (part "M09"))
    )
    (comp (ref "JP5")
      (value "M07")
      (footprint "eagle-import:1X07")
      (libsource (lib "eagle-import") (part "M07"))
    )
    (comp (ref "JP6")
      (value "M03PTH")
      (footprint "eagle-import:1X03")
      (libsource (lib "eagle-import") (part "M03PTH"))
    )
    (comp (ref "JP9")
      (value "M03PTH")
      (footprint "eagle-import:1X03")
      (libsource (lib "eagle-import") (part "M03PTH"))
    )
    (comp (ref "JP12")
      (value "M05PTH")
      (footprint "eagle-import:1X05")
      (libsource (lib "eagle-import") (part "M05PTH"))
    )
    (comp (ref "JP13")
      (value "M03PTH")
      (footprint "eagle-import:1X03")
      (libsource (lib "eagle-import") (part "M03PTH"))
    )
    (comp (ref "LD1")
      (value "DUOLED-RY-C")
      (footprint "eagle-import:DUOLED-C-5MM")
      (libsource (lib "eagle-import") (part "DUOLED-RY-C"))
    )
    (comp (ref "LD2")
      (value "DUOLED-RY-C")
      (footprint "eagle-import:DUOLED-C-5MM")
      (libsource (lib "eagle-import") (part "DUOLED-RY-C"))
    )
    (comp (ref "OUT_A")
      (value "THONKICONN")
      (footprint "eagle-import:THONKICONN")
      (libsource (lib "eagle-import") (part "THONKICONN"))
    )
    (comp (ref "OUT_B")
      (value "THONKICONN")
      (footprint "eagle-import:THONKICONN")
      (libsource (lib "eagle-import") (part "THONKICONN"))
    )
    (comp (ref "POT_EXPA")
      (value "POT-ALPS-RK09L1140")
      (footprint "eagle-import:POT-ALPS-RK09L1140")
      (libsource (lib "eagle-import") (part "POT-ALPS-RK09L1140"))
    )
    (comp (ref "POT_EXPB")
      (value "POT-ALPS-RK09L1140")
      (footprint "eagle-import:POT-ALPS-RK09L1140")
      (libsource (lib "eagle-import") (part "POT-ALPS-RK09L1140"))
    )
    (comp (ref "POT_LINA")
      (value "POT-ALPS-RK09L1140")
      (footprint "eagle-import:POT-ALPS-RK09L1140")
      (libsource (lib "eagle-import") (part "POT-ALPS-RK09L1140"))
    )
    (comp (ref "POT_LINB")
      (value "POT-ALPS-RK09L1140")
      (footprint "eagle-import:POT-ALPS-RK09L1140")
      (libsource (lib "eagle-import") (part "POT-ALPS-RK09L1140"))
    )
    (comp (ref "POT_LINBIASA")
      (value "POT-ALPS-RK09L1140")
      (footprint "eagle-import:POT-ALPS-RK09L1140")
      (libsource (lib "eagle-import") (part "POT-ALPS-RK09L1140"))
    )
    (comp (ref "POT_LINBIASB")
      (value "POT-ALPS-RK09L1140")
      (footprint "eagle-import:POT-ALPS-RK09L1140")
      (libsource (lib "eagle-import") (part "POT-ALPS-RK09L1140"))
    )
    (comp (ref "S1")
      (value "SWITCH-SPST")
      (footprint "eagle-import:SWITCH-SPDT-SALECOM-T8014")
      (libsource (lib "eagle-import") (part "SWITCH-SPST"))
    )
    (comp (ref "S2")
      (value "SWITCH-SPST")
      (footprint "eagle-import:SWITCH-SPDT-SALECOM-T8014")
      (libsource (lib "eagle-import") (part "SWITCH-SPST"))
    )
    (comp (ref "140K")
      (value "100k")
      (footprint "eagle-import:0603")
      (libsource (lib "eagle-import") (part "R-EU_0603"))
    )
    (comp (ref "140K1")
      (value "100k")
      (footprint "eagle-import:0603")
      (libsource (lib "eagle-import") (part "R-EU_0603"))
    )
    (comp (ref "140K2")
      (value "100k")
      (footprint "eagle-import:0603")
      (libsource (lib "eagle-import") (part "R-EU_0603"))
    )
    (comp (ref "140K3")
      (value "100k")
      (footprint "eagle-import:0603")
      (libsource (lib "eagle-import") (part "R-EU_0603"))
    )
    (comp (ref "C1")
      (value "4u7")
      (footprint "eagle-import:C0603K")
      (libsource (lib "eagle-import") (part "resistor_C-EUC0603K"))
    )
    (comp (ref "C2")
      (value "560p")
      (footprint "eagle-import:C0603K")
      (libsource (lib "eagle-import") (part "resistor_C-EUC0603K"))
    )
    (comp (ref "C6")
      (value "100p")
      (footprint "eagle-import:C0603K")
      (libsource (lib "eagle-import") (part "resistor_C-EUC0603K"))
    )
    (comp (ref "C7")
      (value "560p")
      (footprint "eagle-import:C0603K")
      (libsource (lib "eagle-import") (part "resistor_C-EUC0603K"))
    )
    (comp (ref "C8")
      (value "100p")
      (footprint "eagle-import:C0603K")
      (libsource (lib "eagle-import") (part "resistor_C-EUC0603K"))
    )
    (comp (ref "C13")
      (value "100p")
      (footprint "eagle-import:C0603K")
      (libsource (lib "eagle-import") (part "resistor_C-EUC0603K"))
    )
    (comp (ref "C17")
      (value "560p")
      (footprint "eagle-import:C0603K")
      (libsource (lib "eagle-import") (part "resistor_C-EUC0603K"))
    )
    (comp (ref "C18")
      (value "100p")
      (footprint "eagle-import:C0603K")
      (libsource (lib "eagle-import") (part "resistor_C-EUC0603K"))
    )
    (comp (ref "C19")
      (value "560p")
      (footprint "eagle-import:C0603K")
      (libsource (lib "eagle-import") (part "resistor_C-EUC0603K"))
    )
    (comp (ref "C20")
      (value "4u7")
      (footprint "eagle-import:C0603K")
      (libsource (lib "eagle-import") (part "resistor_C-EUC0603K"))
    )
    (comp (ref "C36")
      (value "100n")
      (footprint "eagle-import:C0603K")
      (libsource (lib "eagle-import") (part "rcl@1_C-EUC0603K"))
    )
    (comp (ref "C37")
      (value "100n")
      (footprint "eagle-import:C0603K")
      (libsource (lib "eagle-import") (part "rcl@1_C-EUC0603K"))
    )
    (comp (ref "C38")
      (value "100n")
      (footprint "eagle-import:C0603K")
      (libsource (lib "eagle-import") (part "rcl@1_C-EUC0603K"))
    )
    (comp (ref "C39")
      (value "100n")
      (footprint "eagle-import:C0603K")
      (libsource (lib "eagle-import") (part "rcl@1_C-EUC0603K"))
    )
    (comp (ref "C44")
      (value "100n")
      (footprint "eagle-import:C0603K")
      (libsource (lib "eagle-import") (part "rcl@1_C-EUC0603K"))
    )
    (comp (ref "C45")
      (value "100n")
      (footprint "eagle-import:C0603K")
      (libsource (lib "eagle-import") (part "rcl@1_C-EUC0603K"))
    )
    (comp (ref "IC7")
      (value "TL074D")
      (footprint "eagle-import:SO14")
      (fields (field (name "OC_FARNELL") "unknown"))
      (libsource (lib "eagle-import") (part "TL074D"))
    )
    (comp (ref "IC10")
      (value "TL074D")
      (footprint "eagle-import:SO14")
      (fields (field (name "OC_FARNELL") "unknown"))
      (libsource (lib "eagle-import") (part "TL074D"))
    )
    (comp (ref "IC11")
      (value "TL072D")
      (footprint "eagle-import:SO08")
      (fields (field (name "OC_FARNELL") "unknown"))
      (libsource (lib "eagle-import") (part "TL072D"))
    )
    (comp (ref "OFFSET_LINA")
      (value "R-TRIMM64W")
      (footprint "eagle-import:RTRIM64W")
      (libsource (lib "eagle-import") (part "R-TRIMM64W"))
    )
    (comp (ref "OFFSET_LINB")
      (value "R-TRIMM64W")
      (footprint "eagle-import:RTRIM64W")
      (libsource (lib "eagle-import") (part "R-TRIMM64W"))
    )
    (comp (ref "R13")
      (value "10k")
      (footprint "eagle-import:0603")
      (libsource (lib "eagle-import") (part "R-EU_0603"))
    )
    (comp (ref "R16")
      (value "100k")
      (footprint "eagle-import:0603")
      (libsource (lib "eagle-import") (part "R-EU_0603"))
    )
    (comp (ref "R18")
      (value "100k")
      (footprint "eagle-import:0603")
      (libsource (lib "eagle-import") (part "R-EU_0603"))
    )
    (comp (ref "R32")
      (value "100k")
      (footprint "eagle-import:0603")
      (libsource (lib "eagle-import") (part "R-EU_0603"))
    )
    (comp (ref "R33")
      (value "100k")
      (footprint "eagle-import:0603")
      (libsource (lib "eagle-import") (part "R-EU_0603"))
    )
    (comp (ref "R34")
      (value "140k")
      (footprint "eagle-import:0603")
      (libsource (lib "eagle-import") (part "R-EU_0603"))
    )
    (comp (ref "R35")
      (value "500")
      (footprint "eagle-import:0603")
      (libsource (lib "eagle-import") (part "R-EU_0603"))
    )
    (comp (ref "R37")
      (value "100k")
      (footprint "eagle-import:0603")
      (libsource (lib "eagle-import") (part "R-EU_0603"))
    )
    (comp (ref "R55")
      (value "100k")
      (footprint "eagle-import:0603")
      (libsource (lib "eagle-import") (part "R-EU_0603"))
    )
    (comp (ref "R58")
      (value "100k")
      (footprint "eagle-import:0603")
      (libsource (lib "eagle-import") (part "R-EU_0603"))
    )
    (comp (ref "R59")
      (value "140k")
      (footprint "eagle-import:0603")
      (libsource (lib "eagle-import") (part "R-EU_0603"))
    )
    (comp (ref "R60")
      (value "500")
      (footprint "eagle-import:0603")
      (libsource (lib "eagle-import") (part "R-EU_0603"))
    )
    (comp (ref "R61")
      (value "100k")
      (footprint "eagle-import:0603")
      (libsource (lib "eagle-import") (part "R-EU_0603"))
    )
    (comp (ref "R83")
      (value "100k")
      (footprint "eagle-import:0603")
      (libsource (lib "eagle-import") (part "R-EU_0603"))
    )
    (comp (ref "R84")
      (value "140k")
      (footprint "eagle-import:0603")
      (libsource (lib "eagle-import") (part "R-EU_0603"))
    )
    (comp (ref "R85")
      (value "500")
      (footprint "eagle-import:0603")
      (libsource (lib "eagle-import") (part "R-EU_0603"))
    )
    (comp (ref "R86")
      (value "100k")
      (footprint "eagle-import:0603")
      (libsource (lib "eagle-import") (part "R-EU_0603"))
    )
    (comp (ref "R87")
      (value "100k")
      (footprint "eagle-import:0603")
      (libsource (lib "eagle-import") (part "R-EU_0603"))
    )
    (comp (ref "R88")
      (value "100k")
      (footprint "eagle-import:0603")
      (libsource (lib "eagle-import") (part "R-EU_0603"))
    )
    (comp (ref "R89")
      (value "140k")
      (footprint "eagle-import:0603")
      (libsource (lib "eagle-import") (part "R-EU_0603"))
    )
    (comp (ref "R90")
      (value "500")
      (footprint "eagle-import:0603")
      (libsource (lib "eagle-import") (part "R-EU_0603"))
    )
    (comp (ref "R91")
      (value "100k")
      (footprint "eagle-import:0603")
      (libsource (lib "eagle-import") (part "R-EU_0603"))
    )
    (comp (ref "R92")
      (value "100k")
      (footprint "eagle-import:0603")
      (libsource (lib "eagle-import") (part "R-EU_0603"))
    )
    (comp (ref "R93")
      (value "10k")
      (footprint "eagle-import:0603")
      (libsource (lib "eagle-import") (part "R-EU_0603"))
    )
    (comp (ref "C9")
      (value "4u7")
      (footprint "eagle-import:C0603K")
      (libsource (lib "eagle-import") (part "resistor_C-EUC0603K"))
    )
    (comp (ref "C24")
      (value "4u7")
      (footprint "eagle-import:C0603K")
      (libsource (lib "eagle-import") (part "resistor_C-EUC0603K"))
    )
    (comp (ref "C26")
      (value "100n")
      (footprint "eagle-import:C0603K")
      (libsource (lib "eagle-import") (part "C-EUC0603K"))
    )
    (comp (ref "C27")
      (value "100n")
      (footprint "eagle-import:C0603K")
      (libsource (lib "eagle-import") (part "C-EUC0603K"))
    )
    (comp (ref "C28")
      (value "100n")
      (footprint "eagle-import:C0603K")
      (libsource (lib "eagle-import") (part "C-EUC0603K"))
    )
    (comp (ref "C29")
      (value "100n")
      (footprint "eagle-import:C0603K")
      (libsource (lib "eagle-import") (part "C-EUC0603K"))
    )
    (comp (ref "C30")
      (value "100n")
      (footprint "eagle-import:C0603K")
      (libsource (lib "eagle-import") (part "C-EUC0603K"))
    )
    (comp (ref "C31")
      (value "100n")
      (footprint "eagle-import:C0603K")
      (libsource (lib "eagle-import") (part "C-EUC0603K"))
    )
    (comp (ref "IC3")
      (value "TL074D")
      (footprint "eagle-import:SO14")
      (libsource (lib "eagle-import") (part "TL074D"))
    )
    (comp (ref "IC12")
      (value "QUAD_OPAMPD")
      (footprint "eagle-import:SO14")
      (libsource (lib "eagle-import") (part "QUAD_OPAMPD"))
    )
    (comp (ref "IC14")
      (value "QUAD_OPAMPD")
      (footprint "eagle-import:SO14")
      (libsource (lib "eagle-import") (part "QUAD_OPAMPD"))
    )
    (comp (ref "OFFSET_REF")
      (value "R-TRIMM64W")
      (footprint "eagle-import:RTRIM64W")
      (libsource (lib "eagle-import") (part "R-TRIMM64W"))
    )
    (comp (ref "OFFSET_REFB")
      (value "R-TRIMM64W")
      (footprint "eagle-import:RTRIM64W")
      (libsource (lib "eagle-import") (part "R-TRIMM64W"))
    )
    (comp (ref "R2")
      (value "10k")
      (footprint "eagle-import:0603")
      (libsource (lib "eagle-import") (part "R-EU_0603"))
    )
    (comp (ref "R15")
      (value "100k")
      (footprint "eagle-import:0603")
      (libsource (lib "eagle-import") (part "R-EU_0603"))
    )
    (comp (ref "R17")
      (value "100k")
      (footprint "eagle-import:0603")
      (libsource (lib "eagle-import") (part "R-EU_0603"))
    )
    (comp (ref "R19")
      (value "100k")
      (footprint "eagle-import:0603")
      (libsource (lib "eagle-import") (part "R-EU_0603"))
    )
    (comp (ref "R23")
      (value "100k")
      (footprint "eagle-import:0603")
      (libsource (lib "eagle-import") (part "R-EU_0603"))
    )
    (comp (ref "R25")
      (value "100k")
      (footprint "eagle-import:0603")
      (libsource (lib "eagle-import") (part "R-EU_0603"))
    )
    (comp (ref "R38")
      (value "100k")
      (footprint "eagle-import:0603")
      (libsource (lib "eagle-import") (part "R-EU_0603"))
    )
    (comp (ref "R39")
      (value "100k")
      (footprint "eagle-import:0603")
      (libsource (lib "eagle-import") (part "R-EU_0603"))
    )
    (comp (ref "R40")
      (value "100k")
      (footprint "eagle-import:0603")
      (libsource (lib "eagle-import") (part "R-EU_0603"))
    )
    (comp (ref "R41")
      (value "100k")
      (footprint "eagle-import:0603")
      (libsource (lib "eagle-import") (part "R-EU_0603"))
    )
    (comp (ref "R42")
      (value "100k")
      (footprint "eagle-import:0603")
      (libsource (lib "eagle-import") (part "R-EU_0603"))
    )
    (comp (ref "R46")
      (value "100k")
      (footprint "eagle-import:0603")
      (libsource (lib "eagle-import") (part "R-EU_0603"))
    )
    (comp (ref "R95")
      (value "100k")
      (footprint "eagle-import:0603")
      (libsource (lib "eagle-import") (part "R-EU_0603"))
    )
    (comp (ref "R96")
      (value "100k")
      (footprint "eagle-import:0603")
      (libsource (lib "eagle-import") (part "R-EU_0603"))
    )
    (comp (ref "R97")
      (value "100k")
      (footprint "eagle-import:0603")
      (libsource (lib "eagle-import") (part "R-EU_0603"))
    )
    (comp (ref "R98")
      (value "100k")
      (footprint "eagle-import:0603")
      (libsource (lib "eagle-import") (part "R-EU_0603"))
    )
    (comp (ref "R99")
      (value "68k")
      (footprint "eagle-import:0603")
      (libsource (lib "eagle-import") (part "R-EU_0603"))
    )
    (comp (ref "R100")
      (value "100k")
      (footprint "eagle-import:0603")
      (libsource (lib "eagle-import") (part "R-EU_0603"))
    )
    (comp (ref "R101")
      (value "100k")
      (footprint "eagle-import:0603")
      (libsource (lib "eagle-import") (part "R-EU_0603"))
    )
    (comp (ref "R102")
      (value "100k")
      (footprint "eagle-import:0603")
      (libsource (lib "eagle-import") (part "R-EU_0603"))
    )
    (comp (ref "R103")
      (value "100k")
      (footprint "eagle-import:0603")
      (libsource (lib "eagle-import") (part "R-EU_0603"))
    )
    (comp (ref "R104")
      (value "100k")
      (footprint "eagle-import:0603")
      (libsource (lib "eagle-import") (part "R-EU_0603"))
    )
    (comp (ref "R105")
      (value "100k")
      (footprint "eagle-import:0603")
      (libsource (lib "eagle-import") (part "R-EU_0603"))
    )
    (comp (ref "R106")
      (value "10k")
      (footprint "eagle-import:0603")
      (libsource (lib "eagle-import") (part "R-EU_0603"))
    )
    (comp (ref "R107")
      (value "100k")
      (footprint "eagle-import:0603")
      (libsource (lib "eagle-import") (part "R-EU_0603"))
    )
    (comp (ref "R108")
      (value "68k")
      (footprint "eagle-import:0603")
      (libsource (lib "eagle-import") (part "R-EU_0603"))
    )
    (comp (ref "R109")
      (value "100k")
      (footprint "eagle-import:0603")
      (libsource (lib "eagle-import") (part "R-EU_0603"))
    )
    (comp (ref "R129")
      (value "10k")
      (footprint "eagle-import:0603")
      (libsource (lib "eagle-import") (part "R-EU_0603"))
    )
    (comp (ref "R130")
      (value "10k")
      (footprint "eagle-import:0603")
      (libsource (lib "eagle-import") (part "R-EU_0603"))
    )
    (comp (ref "R131")
      (value "100k")
      (footprint "eagle-import:0603")
      (libsource (lib "eagle-import") (part "R-EU_0603"))
    )
  )
  (nets
    (net (code "1") (name "+12V") (class "Default")
      (node (ref "C21") (pin "1") (pinfunction "1_1") (pintype "passive"))
      (node (ref "C23") (pin "1") (pinfunction "1_1") (pintype "passive"))
      (node (ref "C26") (pin "1") (pinfunction "1_1") (pintype "passive"))
      (node (ref "C28") (pin "1") (pinfunction "1_1") (pintype "passive"))
      (node (ref "C30") (pin "1") (pinfunction "1_1") (pintype "passive"))
      (node (ref "C32") (pin "1") (pinfunction "1_1") (pintype "passive"))
      (node (ref "C34") (pin "1") (pinfunction "1_1") (pintype "passive"))
      (node (ref "C36") (pin "1") (pinfunction "1_1") (pintype "passive"))
      (node (ref "C38") (pin "1") (pinfunction "1_1") (pintype "passive"))
      (node (ref "C40") (pin "1") (pinfunction "1_1") (pintype "passive"))
      (node (ref "C42") (pin "1") (pinfunction "1_1") (pintype "passive"))
      (node (ref "C44") (pin "1") (pinfunction "1_1") (pintype "passive"))
      (node (ref "C46") (pin "1") (pinfunction "1_1") (pintype "passive"))
      (node (ref "IC1") (pin "4") (pinfunction "V+_4") (pintype "power_in"))
      (node (ref "IC10") (pin "4") (pinfunction "V+_4") (pintype "power_in"))
      (node (ref "IC11") (pin "8") (pinfunction "V+_8") (pintype "power_in"))
      (node (ref "IC12") (pin "4") (pinfunction "V+_4") (pintype "power_in"))
      (node (ref "IC14") (pin "4") (pinfunction "V+_4") (pintype "power_in"))
      (node (ref "IC2") (pin "16") (pinfunction "V+_16") (pintype "power_in"))
      (node (ref "IC3") (pin "4") (pinfunction "V+_4") (pintype "power_in"))
      (node (ref "IC4") (pin "8") (pinfunction "V+_8") (pintype "power_in"))
      (node (ref "IC5") (pin "4") (pinfunction "V+_4") (pintype "power_in"))
      (node (ref "IC6") (pin "16") (pinfunction "V+_16") (pintype "power_in"))
      (node (ref "IC7") (pin "4") (pinfunction "V+_4") (pintype "power_in"))
      (node (ref "IC8") (pin "4") (pinfunction "V+_4") (pintype "power_in"))
      (node (ref "IC9") (pin "4") (pinfunction "V+_4") (pintype "power_in"))
      (node (ref "Q9") (pin "2") (pinfunction "S_2") (pintype "passive"))
      (node (ref "R106") (pin "2") (pinfunction "2_2") (pintype "passive"))
      (node (ref "R110") (pin "2") (pinfunction "2_2") (pintype "passive"))
      (node (ref "R112") (pin "2") (pinfunction "2_2") (pintype "passive"))
      (node (ref "R114") (pin "2") (pinfunction "2_2") (pintype "passive"))
      (node (ref "R117") (pin "1") (pinfunction "1_1") (pintype "passive"))
      (node (ref "R121") (pin "1") (pinfunction "1_1") (pintype "passive"))
      (node (ref "R124") (pin "2") (pinfunction "2_2") (pintype "passive"))
      (node (ref "R127") (pin "2") (pinfunction "2_2") (pintype "passive"))
      (node (ref "R13") (pin "2") (pinfunction "2_2") (pintype "passive"))
      (node (ref "R2") (pin "2") (pinfunction "2_2") (pintype "passive"))
      (node (ref "R62") (pin "2") (pinfunction "2_2") (pintype "passive"))
      (node (ref "R93") (pin "2") (pinfunction "2_2") (pintype "passive"))
      (node (ref "R94") (pin "2") (pinfunction "2_2") (pintype "passive"))
    )
    (net (code "2") (name "-12V") (class "Default")
      (node (ref "C22") (pin "2") (pinfunction "2_2") (pintype "passive"))
      (node (ref "C25") (pin "1") (pinfunction "1_1") (pintype "passive"))
      (node (ref "C27") (pin "1") (pinfunction "1_1") (pintype "passive"))
      (node (ref "C29") (pin "1") (pinfunction "1_1") (pintype "passive"))
      (node (ref "C31") (pin "1") (pinfunction "1_1") (pintype "passive"))
      (node (ref "C33") (pin "1") (pinfunction "1_1") (pintype "passive"))
      (node (ref "C35") (pin "1") (pinfunction "1_1") (pintype "passive"))
      (node (ref "C37") (pin "1") (pinfunction "1_1") (pintype "passive"))
      (node (ref "C39") (pin "1") (pinfunction "1_1") (pintype "passive"))
      (node (ref "C41") (pin "1") (pinfunction "1_1") (pintype "passive"))
      (node (ref "C43") (pin "2") (pinfunction "2_2") (pintype "passive"))
      (node (ref "C45") (pin "1") (pinfunction "1_1") (pintype "passive"))
      (node (ref "C47") (pin "1") (pinfunction "1_1") (pintype "passive"))
      (node (ref "D7") (pin "3") (pinfunction "AA_3") (pintype "passive"))
      (node (ref "D9") (pin "3") (pinfunction "AA_3") (pintype "passive"))
      (node (ref "IC1") (pin "11") (pinfunction "V-_11") (pintype "power_in"))
      (node (ref "IC10") (pin "11") (pinfunction "V-_11") (pintype "power_in"))
      (node (ref "IC11") (pin "4") (pinfunction "V-_4") (pintype "power_in"))
      (node (ref "IC12") (pin "11") (pinfunction "V-_11") (pintype "power_in"))
      (node (ref "IC14") (pin "11") (pinfunction "V-_11") (pintype "power_in"))
      (node (ref "IC2") (pin "9") (pinfunction "V-_9") (pintype "power_in"))
      (node (ref "IC3") (pin "11") (pinfunction "V-_11") (pintype "power_in"))
      (node (ref "IC4") (pin "4") (pinfunction "V-_4") (pintype "power_in"))
      (node (ref "IC5") (pin "11") (pinfunction "V-_11") (pintype "power_in"))
      (node (ref "IC6") (pin "9") (pinfunction "V-_9") (pintype "power_in"))
      (node (ref "IC7") (pin "11") (pinfunction "V-_11") (pintype "power_in"))
      (node (ref "IC8") (pin "11") (pinfunction "V-_11") (pintype "power_in"))
      (node (ref "IC9") (pin "11") (pinfunction "V-_11") (pintype "power_in"))
      (node (ref "Q10") (pin "2") (pinfunction "S_2") (pintype "passive"))
      (node (ref "R118") (pin "2") (pinfunction "2_2") (pintype "passive"))
      (node (ref "R122") (pin "2") (pinfunction "2_2") (pintype "passive"))
      (node (ref "R37") (pin "2") (pinfunction "2_2") (pintype "passive"))
      (node (ref "R61") (pin "2") (pinfunction "2_2") (pintype "passive"))
      (node (ref "R63") (pin "1") (pinfunction "1_1") (pintype "passive"))
      (node (ref "R86") (pin "2") (pinfunction "2_2") (pintype "passive"))
      (node (ref "R91") (pin "2") (pinfunction "2_2") (pintype "passive"))
    )
    (net (code "3") (name "CLAMP_REF") (class "Default")
      (node (ref "D1") (pin "3") (pinfunction "AA_3") (pintype "passive"))
      (node (ref "D2") (pin "3") (pinfunction "AA_3") (pintype "passive"))
      (node (ref "IC4") (pin "1") (pinfunction "OUT_1") (pintype "output"))
      (node (ref "IC4") (pin "2") (pinfunction "-IN_2") (pintype "input"))
    )
    (net (code "4") (name "CV_EPXB") (class "Default")
      (node (ref "JP12") (pin "2") (pinfunction "2_2") (pintype "passive"))
    )
    (net (code "5") (name "CV_EXPA") (class "Default")
      (node (ref "CV_EXP_A") (pin "P$3") (pinfunction "3_P$3") (pintype "passive"))
      (node (ref "CV_LIN_A") (pin "P$2") (pinfunction "4_P$2") (pintype "passive"))
      (node (ref "JP11") (pin "4") (pinfunction "4_4") (pintype "passive"))
      (node (ref "JP12") (pin "4") (pinfunction "4_4") (pintype "passive"))
      (node (ref "R65") (pin "1") (pinfunction "1_1") (pintype "passive"))
    )
    (net (code "6") (name "CV_EXPB") (class "Default")
      (node (ref "CV_EXP_B") (pin "P$3") (pinfunction "3_P$3") (pintype "passive"))
      (node (ref "CV_LIN_B") (pin "P$2") (pinfunction "4_P$2") (pintype "passive"))
      (node (ref "JP11") (pin "2") (pinfunction "2_2") (pintype "passive"))
      (node (ref "R74") (pin "1") (pinfunction "1_1") (pintype "passive"))
    )
    (net (code "7") (name "CV_LINA") (class "Default")
      (node (ref "CV_EXP_A") (pin "P$2") (pinfunction "4_P$2") (pintype "passive"))
      (node (ref "CV_LIN_A") (pin "P$3") (pinfunction "3_P$3") (pintype "passive"))
      (node (ref "JP11") (pin "5") (pinfunction "5_5") (pintype "passive"))
      (node (ref "JP12") (pin "5") (pinfunction "5_5") (pintype "passive"))
      (node (ref "R52") (pin "1") (pinfunction "1_1") (pintype "passive"))
    )
    (net (code "8") (name "CV_LINB") (class "Default")
      (node (ref "CV_EXP_B") (pin "P$2") (pinfunction "4_P$2") (pintype "passive"))
      (node (ref "CV_LIN_B") (pin "P$3") (pinfunction "3_P$3") (pintype "passive"))
      (node (ref "JP11") (pin "1") (pinfunction "1_1") (pintype "passive"))
      (node (ref "JP12") (pin "1") (pinfunction "1_1") (pintype "passive"))
      (node (ref "R72") (pin "1") (pinfunction "1_1") (pintype "passive"))
    )
    (net (code "9") (name "CV_SUM+_A") (class "Default")
      (node (ref "IC14") (pin "7") (pinfunction "OUT_7") (pintype "output"))
      (node (ref "R38") (pin "1") (pinfunction "1_1") (pintype "passive"))
      (node (ref "R51") (pin "2") (pinfunction "2_2") (pintype "passive"))
    )
    (net (code "10") (name "CV_SUM+_B") (class "Default")
      (node (ref "IC3") (pin "8") (pinfunction "OUT_8") (pintype "output"))
      (node (ref "R69") (pin "2") (pinfunction "2_2") (pintype "passive"))
      (node (ref "R95") (pin "2") (pinfunction "2_2") (pintype "passive"))
    )
    (net (code "11") (name "CV_SUM-_A") (class "Default")
      (node (ref "IC14") (pin "8") (pinfunction "OUT_8") (pintype "output"))
      (node (ref "R41") (pin "1") (pinfunction "1_1") (pintype "passive"))
      (node (ref "R44") (pin "2") (pinfunction "2_2") (pintype "passive"))
    )
    (net (code "12") (name "CV_SUM-_B") (class "Default")
      (node (ref "IC3") (pin "14") (pinfunction "OUT_14") (pintype "output"))
      (node (ref "R105") (pin "2") (pinfunction "2_2") (pintype "passive"))
      (node (ref "R70") (pin "2") (pinfunction "2_2") (pintype "passive"))
    )
    (net (code "13") (name "EXP_NEG_A") (class "Default")
      (node (ref "D5") (pin "2") (pinfunction "C2_2") (pintype "passive"))
      (node (ref "R40") (pin "2") (pinfunction "2_2") (pintype "passive"))
    )
    (net (code "14") (name "EXP_NEG_B") (class "Default")
      (node (ref "D6") (pin "2") (pinfunction "C2_2") (pintype "passive"))
      (node (ref "R107") (pin "2") (pinfunction "2_2") (pintype "passive"))
    )
    (net (code "15") (name "EXP_POS_A") (class "Default")
      (node (ref "D5") (pin "1") (pinfunction "A1_1") (pintype "passive"))
      (node (ref "R42") (pin "2") (pinfunction "2_2") (pintype "passive"))
    )
    (net (code "16") (name "EXP_POS_B") (class "Default")
      (node (ref "D6") (pin "1") (pinfunction "A1_1") (pintype "passive"))
      (node (ref "R101") (pin "2") (pinfunction "2_2") (pintype "passive"))
    )
    (net (code "17") (name "GND") (class "Default")
      (node (ref "140K") (pin "1") (pinfunction "1_1") (pintype "passive"))
      (node (ref "140K1") (pin "1") (pinfunction "1_1") (pintype "passive"))
      (node (ref "140K2") (pin "1") (pinfunction "1_1") (pintype "passive"))
      (node (ref "140K3") (pin "1") (pinfunction "1_1") (pintype "passive"))
      (node (ref "C1") (pin "2") (pinfunction "2_2") (pintype "passive"))
      (node (ref "C10") (pin "2") (pinfunction "2_2") (pintype "passive"))
      (node (ref "C11") (pin "2") (pinfunction "2_2") (pintype "passive"))
      (node (ref "C15") (pin "2") (pinfunction "2_2") (pintype "passive"))
      (node (ref "C17") (pin "2") (pinfunction "2_2") (pintype "passive"))
      (node (ref "C19") (pin "2") (pinfunction "2_2") (pintype "passive"))
      (node (ref "C2") (pin "2") (pinfunction "2_2") (pintype "passive"))
      (node (ref "C20") (pin "2") (pinfunction "2_2") (pintype "passive"))
      (node (ref "C21") (pin "2") (pinfunction "2_2") (pintype "passive"))
      (node (ref "C22") (pin "1") (pinfunction "1_1") (pintype "passive"))
      (node (ref "C23") (pin "2") (pinfunction "2_2") (pintype "passive"))
      (node (ref "C24") (pin "2") (pinfunction "2_2") (pintype "passive"))
      (node (ref "C25") (pin "2") (pinfunction "2_2") (pintype "passive"))
      (node (ref "C26") (pin "2") (pinfunction "2_2") (pintype "passive"))
      (node (ref "C27") (pin "2") (pinfunction "2_2") (pintype "passive"))
      (node (ref "C28") (pin "2") (pinfunction "2_2") (pintype "passive"))
      (node (ref "C29") (pin "2") (pinfunction "2_2") (pintype "passive"))
      (node (ref "C3") (pin "2") (pinfunction "2_2") (pintype "passive"))
      (node (ref "C30") (pin "2") (pinfunction "2_2") (pintype "passive"))
      (node (ref "C31") (pin "2") (pinfunction "2_2") (pintype "passive"))
      (node (ref "C32") (pin "2") (pinfunction "2_2") (pintype "passive"))
      (node (ref "C33") (pin "2") (pinfunction "2_2") (pintype "passive"))
      (node (ref "C34") (pin "2") (pinfunction "2_2") (pintype "passive"))
      (node (ref "C35") (pin "2") (pinfunction "2_2") (pintype "passive"))
      (node (ref "C36") (pin "2") (pinfunction "2_2") (pintype "passive"))
      (node (ref "C37") (pin "2") (pinfunction "2_2") (pintype "passive"))
      (node (ref "C38") (pin "2") (pinfunction "2_2") (pintype "passive"))
      (node (ref "C39") (pin "2") (pinfunction "2_2") (pintype "passive"))
      (node (ref "C40") (pin "2") (pinfunction "2_2") (pintype "passive"))
      (node (ref "C41") (pin "2") (pinfunction "2_2") (pintype "passive"))
      (node (ref "C42") (pin "2") (pinfunction "2_2") (pintype "passive"))
      (node (ref "C43") (pin "1") (pinfunction "1_1") (pintype "passive"))
      (node (ref "C44") (pin "2") (pinfunction "2_2") (pintype "passive"))
      (node (ref "C45") (pin "2") (pinfunction "2_2") (pintype "passive"))
      (node (ref "C46") (pin "2") (pinfunction "2_2") (pintype "passive"))
      (node (ref "C47") (pin "2") (pinfunction "2_2") (pintype "passive"))
      (node (ref "C5") (pin "2") (pinfunction "2_2") (pintype "passive"))
      (node (ref "C7") (pin "2") (pinfunction "2_2") (pintype "passive"))
      (node (ref "C9") (pin "2") (pinfunction "2_2") (pintype "passive"))
      (node (ref "CV_EXP_A") (pin "P$1") (pinfunction "5_P$1") (pintype "passive"))
      (node (ref "CV_EXP_B") (pin "P$1") (pinfunction "5_P$1") (pintype "passive"))
      (node (ref "CV_LIN_A") (pin "P$1") (pinfunction "5_P$1") (pintype "passive"))
      (node (ref "CV_LIN_B") (pin "P$1") (pinfunction "5_P$1") (pintype "passive"))
      (node (ref "D7") (pin "1") (pinfunction "K1_1") (pintype "passive"))
      (node (ref "D7") (pin "2") (pinfunction "K2_2") (pintype "passive"))
      (node (ref "D9") (pin "1") (pinfunction "K1_1") (pintype "passive"))
      (node (ref "D9") (pin "2") (pinfunction "K2_2") (pintype "passive"))
      (node (ref "IC10") (pin "5") (pinfunction "+IN_5") (pintype "input"))
      (node (ref "IC12") (pin "3") (pinfunction "+IN_3") (pintype "input"))
      (node (ref "IC14") (pin "12") (pinfunction "+IN_12") (pintype "input"))
      (node (ref "IC14") (pin "3") (pinfunction "+IN_3") (pintype "input"))
      (node (ref "IC2") (pin "8") (pinfunction "GND_8") (pintype "power_in"))
      (node (ref "IC4") (pin "5") (pinfunction "+IN_5") (pintype "input"))
      (node (ref "IC5") (pin "10") (pinfunction "+IN_10") (pintype "input"))
      (node (ref "IC5") (pin "5") (pinfunction "+IN_5") (pintype "input"))
      (node (ref "IC6") (pin "8") (pinfunction "GND_8") (pintype "power_in"))
      (node (ref "IC7") (pin "5") (pinfunction "+IN_5") (pintype "input"))
      (node (ref "IC8") (pin "10") (pinfunction "+IN_10") (pintype "input"))
      (node (ref "IC8") (pin "5") (pinfunction "+IN_5") (pintype "input"))
      (node (ref "IN_A") (pin "P$1") (pinfunction "5_P$1") (pintype "passive"))
      (node (ref "IN_A") (pin "P$2") (pinfunction "4_P$2") (pintype "passive"))
      (node (ref "IN_B") (pin "P$1") (pinfunction "5_P$1") (pintype "passive"))
      (node (ref "IN_B") (pin "P$2") (pinfunction "4_P$2") (pintype "passive"))
      (node (ref "J2") (pin "4") (pinfunction "4_4") (pintype "passive"))
      (node (ref "JP1") (pin "2") (pinfunction "2_2") (pintype "passive"))
      (node (ref "JP10") (pin "2") (pinfunction "2_2") (pintype "passive"))
      (node (ref "JP11") (pin "3") (pinfunction "3_3") (pintype "passive"))
      (node (ref "JP12") (pin "3") (pinfunction "3_3") (pintype "passive"))
      (node (ref "JP13") (pin "2") (pinfunction "2_2") (pintype "passive"))
      (node (ref "JP14") (pin "2") (pinfunction "2_2") (pintype "passive"))
      (node (ref "JP2") (pin "5") (pinfunction "5_5") (pintype "passive"))
      (node (ref "JP3") (pin "5") (pinfunction "5_5") (pintype "passive"))
      (node (ref "JP4") (pin "4") (pinfunction "4_4") (pintype "passive"))
      (node (ref "JP5") (pin "4") (pinfunction "4_4") (pintype "passive"))
      (node (ref "JP6") (pin "2") (pinfunction "2_2") (pintype "passive"))
      (node (ref "JP7") (pin "4") (pinfunction "4_4") (pintype "passive"))
      (node (ref "JP8") (pin "3") (pinfunction "3_3") (pintype "passive"))
      (node (ref "JP8") (pin "4") (pinfunction "4_4") (pintype "passive"))
      (node (ref "JP8") (pin "5") (pinfunction "5_5") (pintype "passive"))
      (node (ref "JP8") (pin "6") (pinfunction "6_6") (pintype "passive"))
      (node (ref "JP8") (pin "7") (pinfunction "7_7") (pintype "passive"))
      (node (ref "JP8") (pin "8") (pinfunction "8_8") (pintype "passive"))
      (node (ref "JP9") (pin "2") (pinfunction "2_2") (pintype "passive"))
      (node (ref "LD1") (pin "C") (pinfunction "C_C") (pintype "passive"))
      (node (ref "LD2") (pin "C") (pinfunction "C_C") (pintype "passive"))
      (node (ref "OFFSET_LINA") (pin "1") (pinfunction "A_1") (pintype "passive"))
      (node (ref "OFFSET_LINB") (pin "1") (pinfunction "A_1") (pintype "passive"))
      (node (ref "OFFSET_REF") (pin "1") (pinfunction "A_1") (pintype "passive"))
      (node (ref "OFFSET_REFB") (pin "1") (pinfunction "A_1") (pintype "passive"))
      (node (ref "OUT_A") (pin "P$1") (pinfunction "5_P$1") (pintype "passive"))
      (node (ref "OUT_A") (pin "P$2") (pinfunction "4_P$2") (pintype "passive"))
      (node (ref "OUT_B") (pin "P$1") (pinfunction "5_P$1") (pintype "passive"))
      (node (ref "OUT_B") (pin "P$2") (pinfunction "4_P$2") (pintype "passive"))
      (node (ref "POT_EXPA") (pin "2") (pinfunction "2_2") (pintype "bidirectional"))
      (node (ref "POT_EXPB") (pin "2") (pinfunction "2_2") (pintype "bidirectional"))
      (node (ref "POT_LINA") (pin "2") (pinfunction "2_2") (pintype "bidirectional"))
      (node (ref "POT_LINB") (pin "2") (pinfunction "2_2") (pintype "bidirectional"))
      (node (ref "Q1") (pin "C") (pinfunction "C_C") (pintype "passive"))
      (node (ref "Q10") (pin "1") (pinfunction "G_1") (pintype "passive"))
      (node (ref "Q2") (pin "C") (pinfunction "C_C") (pintype "passive"))
      (node (ref "Q3") (pin "C") (pinfunction "C_C") (pintype "passive"))
      (node (ref "Q5") (pin "C") (pinfunction "C_C") (pintype "passive"))
      (node (ref "Q9") (pin "1") (pinfunction "G_1") (pintype "passive"))
      (node (ref "R1") (pin "2") (pinfunction "2_2") (pintype "passive"))
      (node (ref "R109") (pin "1") (pinfunction "1_1") (pintype "passive"))
      (node (ref "R111") (pin "1") (pinfunction "1_1") (pintype "passive"))
      (node (ref "R113") (pin "1") (pinfunction "1_1") (pintype "passive"))
      (node (ref "R119") (pin "2") (pinfunction "2_2") (pintype "passive"))
      (node (ref "R120") (pin "2") (pinfunction "2_2") (pintype "passive"))
      (node (ref "R123") (pin "1") (pinfunction "1_1") (pintype "passive"))
      (node (ref "R126") (pin "1") (pinfunction "1_1") (pintype "passive"))
      (node (ref "R25") (pin "1") (pinfunction "1_1") (pintype "passive"))
      (node (ref "R30") (pin "2") (pinfunction "2_2") (pintype "passive"))
      (node (ref "R46") (pin "1") (pinfunction "1_1") (pintype "passive"))
      (node (ref "R50") (pin "2") (pinfunction "2_2") (pintype "passive"))
      (node (ref "R71") (pin "2") (pinfunction "2_2") (pintype "passive"))
      (node (ref "R96") (pin "1") (pinfunction "1_1") (pintype "passive"))
    )
    (net (code "18") (name "IC2_4") (class "Default")
      (node (ref "C13") (pin "2") (pinfunction "2_2") (pintype "passive"))
      (node (ref "IC2") (pin "4") (pinfunction "OUT_4") (pintype "output"))
      (node (ref "IC7") (pin "9") (pinfunction "-IN_9") (pintype "input"))
      (node (ref "R33") (pin "1") (pinfunction "1_1") (pintype "passive"))
    )
    (net (code "19") (name "IC6_4") (class "Default")
      (node (ref "C18") (pin "2") (pinfunction "2_2") (pintype "passive"))
      (node (ref "IC10") (pin "13") (pinfunction "-IN_13") (pintype "input"))
      (node (ref "IC6") (pin "4") (pinfunction "OUT_4") (pintype "output"))
      (node (ref "R88") (pin "1") (pinfunction "1_1") (pintype "passive"))
    )
    (net (code "20") (name "IC6_13") (class "Default")
      (node (ref "C8") (pin "2") (pinfunction "2_2") (pintype "passive"))
      (node (ref "IC10") (pin "9") (pinfunction "-IN_9") (pintype "input"))
      (node (ref "IC6") (pin "13") (pinfunction "OUT_13") (pintype "output"))
      (node (ref "R83") (pin "1") (pinfunction "1_1") (pintype "passive"))
    )
    (net (code "21") (name "IN1") (class "Default")
      (node (ref "IC8") (pin "1") (pinfunction "OUT_1") (pintype "output"))
      (node (ref "IC8") (pin "2") (pinfunction "-IN_2") (pintype "input"))
      (node (ref "R48") (pin "1") (pinfunction "1_1") (pintype "passive"))
      (node (ref "R57") (pin "1") (pinfunction "1_1") (pintype "passive"))
    )
    (net (code "22") (name "IN2") (class "Default")
      (node (ref "IC5") (pin "1") (pinfunction "OUT_1") (pintype "output"))
      (node (ref "IC5") (pin "2") (pinfunction "-IN_2") (pintype "input"))
      (node (ref "R24") (pin "1") (pinfunction "1_1") (pintype "passive"))
      (node (ref "R9") (pin "1") (pinfunction "1_1") (pintype "passive"))
    )
    (net (code "23") (name "INV_A") (class "Default")
      (node (ref "IC5") (pin "12") (pinfunction "+IN_12") (pintype "input"))
      (node (ref "JP1") (pin "1") (pinfunction "1_1") (pintype "passive"))
      (node (ref "JP6") (pin "1") (pinfunction "1_1") (pintype "passive"))
      (node (ref "R125") (pin "1") (pinfunction "1_1") (pintype "passive"))
      (node (ref "R20") (pin "2") (pinfunction "2_2") (pintype "passive"))
      (node (ref "R30") (pin "1") (pinfunction "1_1") (pintype "passive"))
      (node (ref "S1") (pin "2") (pinfunction "P_2") (pintype "passive"))
    )
    (net (code "24") (name "INV_B") (class "Default")
      (node (ref "IC8") (pin "12") (pinfunction "+IN_12") (pintype "input"))
      (node (ref "JP1") (pin "3") (pinfunction "3_3") (pintype "passive"))
      (node (ref "JP6") (pin "3") (pinfunction "3_3") (pintype "passive"))
      (node (ref "R128") (pin "1") (pinfunction "1_1") (pintype "passive"))
      (node (ref "R66") (pin "2") (pinfunction "2_2") (pintype "passive"))
      (node (ref "R71") (pin "1") (pinfunction "1_1") (pintype "passive"))
      (node (ref "S2") (pin "2") (pinfunction "P_2") (pintype "passive"))
    )
    (net (code "25") (name "IN_A") (class "Default")
      (node (ref "IC5") (pin "3") (pinfunction "+IN_3") (pintype "input"))
      (node (ref "IN_A") (pin "P$3") (pinfunction "3_P$3") (pintype "passive"))
      (node (ref "JP13") (pin "3") (pinfunction "3_3") (pintype "passive"))
      (node (ref "JP14") (pin "3") (pinfunction "3_3") (pintype "passive"))
      (node (ref "R1") (pin "1") (pinfunction "1_1") (pintype "passive"))
    )
    (net (code "26") (name "IN_B") (class "Default")
      (node (ref "IC8") (pin "3") (pinfunction "+IN_3") (pintype "input"))
      (node (ref "IN_B") (pin "P$3") (pinfunction "3_P$3") (pintype "passive"))
      (node (ref "JP13") (pin "1") (pinfunction "1_1") (pintype "passive"))
      (node (ref "JP14") (pin "1") (pinfunction "1_1") (pintype "passive"))
      (node (ref "R50") (pin "1") (pinfunction "1_1") (pintype "passive"))
    )
    (net (code "27") (name "LED_A+") (class "Default")
      (node (ref "J2") (pin "3") (pinfunction "3_3") (pintype "passive"))
      (node (ref "LD1") (pin "AR") (pinfunction "AR_AR") (pintype "passive"))
      (node (ref "Q1") (pin "E") (pinfunction "E_E") (pintype "passive"))
      (node (ref "R114") (pin "1") (pinfunction "1_1") (pintype "passive"))
    )
    (net (code "28") (name "LED_A-") (class "Default")
      (node (ref "J2") (pin "2") (pinfunction "2_2") (pintype "passive"))
      (node (ref "LD1") (pin "AX") (pinfunction "AY_AX") (pintype "passive"))
      (node (ref "Q2") (pin "E") (pinfunction "E_E") (pintype "passive"))
      (node (ref "R124") (pin "1") (pinfunction "1_1") (pintype "passive"))
    )
    (net (code "29") (name "LED_B+") (class "Default")
      (node (ref "J2") (pin "7") (pinfunction "7_7") (pintype "passive"))
      (node (ref "JP7") (pin "1") (pinfunction "1_1") (pintype "passive"))
      (node (ref "LD2") (pin "AR") (pinfunction "AR_AR") (pintype "passive"))
      (node (ref "Q5") (pin "E") (pinfunction "E_E") (pintype "passive"))
      (node (ref "R112") (pin "1") (pinfunction "1_1") (pintype "passive"))
    )
    (net (code "30") (name "LED_B-") (class "Default")
      (node (ref "J2") (pin "6") (pinfunction "6_6") (pintype "passive"))
      (node (ref "JP7") (pin "2") (pinfunction "2_2") (pintype "passive"))
      (node (ref "LD2") (pin "AX") (pinfunction "AY_AX") (pintype "passive"))
      (node (ref "Q3") (pin "E") (pinfunction "E_E") (pintype "passive"))
      (node (ref "R127") (pin "1") (pinfunction "1_1") (pintype "passive"))
    )
    (net (code "31") (name "LIN+_OUT_A") (class "Default")
      (node (ref "C6") (pin "1") (pinfunction "1_1") (pintype "passive"))
      (node (ref "IC2") (pin "14") (pinfunction "CTRL_14") (pintype "input"))
      (node (ref "IC7") (pin "14") (pinfunction "OUT_14") (pintype "output"))
      (node (ref "R17") (pin "2") (pinfunction "2_2") (pintype "passive"))
    )
    (net (code "32") (name "LIN+_OUT_B") (class "Default")
      (node (ref "C18") (pin "1") (pinfunction "1_1") (pintype "passive"))
      (node (ref "IC10") (pin "14") (pinfunction "OUT_14") (pintype "output"))
      (node (ref "IC6") (pin "3") (pinfunction "CTRL_3") (pintype "input"))
      (node (ref "R98") (pin "1") (pinfunction "1_1") (pintype "passive"))
    )
    (net (code "33") (name "LIN-_OUT_A") (class "Default")
      (node (ref "C13") (pin "1") (pinfunction "1_1") (pintype "passive"))
      (node (ref "IC2") (pin "3") (pinfunction "CTRL_3") (pintype "input"))
      (node (ref "IC7") (pin "8") (pinfunction "OUT_8") (pintype "output"))
      (node (ref "R23") (pin "1") (pinfunction "1_1") (pintype "passive"))
    )
    (net (code "34") (name "LIN-_OUT_B") (class "Default")
      (node (ref "C8") (pin "1") (pinfunction "1_1") (pintype "passive"))
      (node (ref "IC10") (pin "8") (pinfunction "OUT_8") (pintype "output"))
      (node (ref "IC6") (pin "14") (pinfunction "CTRL_14") (pintype "input"))
      (node (ref "R104") (pin "1") (pinfunction "1_1") (pintype "passive"))
    )
    (net (code "35") (name "LINBIASA_1") (class "Default")
      (node (ref "JP4") (pin "3") (pinfunction "3_3") (pintype "passive"))
      (node (ref "JP5") (pin "3") (pinfunction "3_3") (pintype "passive"))
      (node (ref "POT_LINBIASA") (pin "1") (pinfunction "1_1") (pintype "bidirectional"))
      (node (ref "R121") (pin "2") (pinfunction "2_2") (pintype "passive"))
    )
    (net (code "36") (name "LINBIASA_2") (class "Default")
      (node (ref "JP4") (pin "2") (pinfunction "2_2") (pintype "passive"))
      (node (ref "JP5") (pin "2") (pinfunction "2_2") (pintype "passive"))
      (node (ref "POT_LINBIASA") (pin "2") (pinfunction "2_2") (pintype "bidirectional"))
      (node (ref "R53") (pin "1") (pinfunction "1_1") (pintype "passive"))
    )
    (net (code "37") (name "LINBIASA_3") (class "Default")
      (node (ref "JP4") (pin "1") (pinfunction "1_1") (pintype "passive"))
      (node (ref "JP5") (pin "1") (pinfunction "1_1") (pintype "passive"))
      (node (ref "POT_LINBIASA") (pin "3") (pinfunction "3_3") (pintype "bidirectional"))
      (node (ref "R122") (pin "1") (pinfunction "1_1") (pintype "passive"))
    )
    (net (code "38") (name "LINBIASB_1") (class "Default")
      (node (ref "JP4") (pin "7") (pinfunction "7_7") (pintype "passive"))
      (node (ref "JP5") (pin "7") (pinfunction "7_7") (pintype "passive"))
      (node (ref "POT_LINBIASB") (pin "1") (pinfunction "1_1") (pintype "bidirectional"))
      (node (ref "R117") (pin "2") (pinfunction "2_2") (pintype "passive"))
    )
    (net (code "39") (name "LINBIASB_2") (class "Default")
      (node (ref "JP4") (pin "6") (pinfunction "6_6") (pintype "passive"))
      (node (ref "JP5") (pin "6") (pinfunction "6_6") (pintype "passive"))
      (node (ref "POT_LINBIASB") (pin "2") (pinfunction "2_2") (pintype "bidirectional"))
      (node (ref "R73") (pin "1") (pinfunction "1_1") (pintype "passive"))
    )
    (net (code "40") (name "LINBIASB_3") (class "Default")
      (node (ref "JP4") (pin "5") (pinfunction "5_5") (pintype "passive"))
      (node (ref "JP5") (pin "5") (pinfunction "5_5") (pintype "passive"))
      (node (ref "POT_LINBIASB") (pin "3") (pinfunction "3_3") (pintype "bidirectional"))
      (node (ref "R118") (pin "1") (pinfunction "1_1") (pintype "passive"))
    )
    (net (code "41") (name "LIN_NEG_A") (class "Default")
      (node (ref "D3") (pin "2") (pinfunction "C2_2") (pintype "passive"))
      (node (ref "R32") (pin "1") (pinfunction "1_1") (pintype "passive"))
    )
    (net (code "42") (name "LIN_NEG_B") (class "Default")
      (node (ref "D4") (pin "2") (pinfunction "C2_2") (pintype "passive"))
      (node (ref "R16") (pin "1") (pinfunction "1_1") (pintype "passive"))
    )
    (net (code "43") (name "LIN_POS_A") (class "Default")
      (node (ref "D3") (pin "1") (pinfunction "A1_1") (pintype "passive"))
      (node (ref "R55") (pin "1") (pinfunction "1_1") (pintype "passive"))
    )
    (net (code "44") (name "LIN_POS_B") (class "Default")
      (node (ref "D4") (pin "1") (pinfunction "A1_1") (pintype "passive"))
      (node (ref "R87") (pin "1") (pinfunction "1_1") (pintype "passive"))
    )
    (net (code "45") (name "Net-(140K-Pad2)") (class "Default")
      (node (ref "140K") (pin "2") (pinfunction "2_2") (pintype "passive"))
      (node (ref "R34") (pin "1") (pinfunction "1_1") (pintype "passive"))
      (node (ref "R37") (pin "1") (pinfunction "1_1") (pintype "passive"))
    )
    (net (code "46") (name "Net-(140K1-Pad2)") (class "Default")
      (node (ref "140K1") (pin "2") (pinfunction "2_2") (pintype "passive"))
      (node (ref "R59") (pin "1") (pinfunction "1_1") (pintype "passive"))
      (node (ref "R61") (pin "1") (pinfunction "1_1") (pintype "passive"))
    )
    (net (code "47") (name "Net-(140K2-Pad2)") (class "Default")
      (node (ref "140K2") (pin "2") (pinfunction "2_2") (pintype "passive"))
      (node (ref "R84") (pin "1") (pinfunction "1_1") (pintype "passive"))
      (node (ref "R86") (pin "1") (pinfunction "1_1") (pintype "passive"))
    )
    (net (code "48") (name "Net-(140K3-Pad2)") (class "Default")
      (node (ref "140K3") (pin "2") (pinfunction "2_2") (pintype "passive"))
      (node (ref "R89") (pin "1") (pinfunction "1_1") (pintype "passive"))
      (node (ref "R91") (pin "1") (pinfunction "1_1") (pintype "passive"))
    )
    (net (code "49") (name "Net-(C2-Pad1)") (class "Default")
      (node (ref "C2") (pin "1") (pinfunction "1_1") (pintype "passive"))
      (node (ref "R35") (pin "1") (pinfunction "1_1") (pintype "passive"))
    )
    (net (code "50") (name "Net-(C3-Pad1)") (class "Default")
      (node (ref "C3") (pin "1") (pinfunction "1_1") (pintype "passive"))
      (node (ref "R6") (pin "1") (pinfunction "1_1") (pintype "passive"))
    )
    (net (code "51") (name "Net-(C5-Pad1)") (class "Default")
      (node (ref "C5") (pin "1") (pinfunction "1_1") (pintype "passive"))
      (node (ref "R11") (pin "1") (pinfunction "1_1") (pintype "passive"))
    )
    (net (code "52") (name "Net-(C7-Pad1)") (class "Default")
      (node (ref "C7") (pin "1") (pinfunction "1_1") (pintype "passive"))
      (node (ref "R60") (pin "1") (pinfunction "1_1") (pintype "passive"))
    )
    (net (code "53") (name "Net-(C11-Pad1)") (class "Default")
      (node (ref "C11") (pin "1") (pinfunction "1_1") (pintype "passive"))
      (node (ref "R47") (pin "1") (pinfunction "1_1") (pintype "passive"))
    )
    (net (code "54") (name "Net-(C15-Pad1)") (class "Default")
      (node (ref "C15") (pin "1") (pinfunction "1_1") (pintype "passive"))
      (node (ref "R56") (pin "1") (pinfunction "1_1") (pintype "passive"))
    )
    (net (code "55") (name "Net-(C17-Pad1)") (class "Default")
      (node (ref "C17") (pin "1") (pinfunction "1_1") (pintype "passive"))
      (node (ref "R85") (pin "1") (pinfunction "1_1") (pintype "passive"))
    )
    (net (code "56") (name "Net-(C19-Pad1)") (class "Default")
      (node (ref "C19") (pin "1") (pinfunction "1_1") (pintype "passive"))
      (node (ref "R90") (pin "1") (pinfunction "1_1") (pintype "passive"))
    )
    (net (code "57") (name "Net-(CLAMP_REF-A)") (class "Default")
      (node (ref "CLAMP_REF") (pin "1") (pinfunction "A_1") (pintype "passive"))
      (node (ref "R63") (pin "2") (pinfunction "2_2") (pintype "passive"))
    )
    (net (code "58") (name "Net-(CLAMP_REF-E)") (class "Default")
      (node (ref "CLAMP_REF") (pin "3") (pinfunction "E_3") (pintype "passive"))
      (node (ref "R62") (pin "1") (pinfunction "1_1") (pintype "passive"))
    )
    (net (code "59") (name "Net-(CLAMP_REF-S)") (class "Default")
      (node (ref "C10") (pin "1") (pinfunction "1_1") (pintype "passive"))
      (node (ref "CLAMP_REF") (pin "2") (pinfunction "S_2") (pintype "passive"))
      (node (ref "IC4") (pin "3") (pinfunction "+IN_3") (pintype "input"))
    )
    (net (code "60") (name "Net-(D1-K1)") (class "Default")
      (node (ref "D1") (pin "1") (pinfunction "K1_1") (pintype "passive"))
      (node (ref "IC2") (pin "6") (pinfunction "CTRL_6") (pintype "input"))
      (node (ref "R44") (pin "1") (pinfunction "1_1") (pintype "passive"))
    )
    (net (code "61") (name "Net-(D1-K2)") (class "Default")
      (node (ref "D1") (pin "2") (pinfunction "K2_2") (pintype "passive"))
      (node (ref "IC2") (pin "11") (pinfunction "CTRL_11") (pintype "input"))
      (node (ref "R51") (pin "1") (pinfunction "1_1") (pintype "passive"))
    )
    (net (code "62") (name "Net-(D2-K1)") (class "Default")
      (node (ref "D2") (pin "1") (pinfunction "K1_1") (pintype "passive"))
      (node (ref "IC6") (pin "6") (pinfunction "CTRL_6") (pintype "input"))
      (node (ref "R70") (pin "1") (pinfunction "1_1") (pintype "passive"))
    )
    (net (code "63") (name "Net-(D2-K2)") (class "Default")
      (node (ref "D2") (pin "2") (pinfunction "K2_2") (pintype "passive"))
      (node (ref "IC6") (pin "11") (pinfunction "CTRL_11") (pintype "input"))
      (node (ref "R69") (pin "1") (pinfunction "1_1") (pintype "passive"))
    )
    (net (code "64") (name "Net-(D3-C1A2)") (class "Default")
      (node (ref "D3") (pin "3") (pinfunction "C1A2_3") (pintype "passive"))
      (node (ref "IC1") (pin "8") (pinfunction "OUT_8") (pintype "output"))
      (node (ref "R4") (pin "2") (pinfunction "2_2") (pintype "passive"))
    )
    (net (code "65") (name "Net-(D4-C1A2)") (class "Default")
      (node (ref "D4") (pin "3") (pinfunction "C1A2_3") (pintype "passive"))
      (node (ref "IC9") (pin "8") (pinfunction "OUT_8") (pintype "output"))
      (node (ref "R79") (pin "2") (pinfunction "2_2") (pintype "passive"))
    )
    (net (code "66") (name "Net-(D5-C1A2)") (class "Default")
      (node (ref "D5") (pin "3") (pinfunction "C1A2_3") (pintype "passive"))
      (node (ref "IC1") (pin "14") (pinfunction "OUT_14") (pintype "output"))
      (node (ref "R21") (pin "2") (pinfunction "2_2") (pintype "passive"))
    )
    (net (code "67") (name "Net-(D6-C1A2)") (class "Default")
      (node (ref "D6") (pin "3") (pinfunction "C1A2_3") (pintype "passive"))
      (node (ref "IC9") (pin "14") (pinfunction "OUT_14") (pintype "output"))
      (node (ref "R76") (pin "2") (pinfunction "2_2") (pintype "passive"))
    )
    (net (code "68") (name "Net-(IC1A-+IN)") (class "Default")
      (node (ref "IC1") (pin "3") (pinfunction "+IN_3") (pintype "input"))
      (node (ref "R52") (pin "2") (pinfunction "2_2") (pintype "passive"))
    )
    (net (code "69") (name "Net-(IC1A--IN)") (class "Default")
      (node (ref "IC1") (pin "1") (pinfunction "OUT_1") (pintype "output"))
      (node (ref "IC1") (pin "2") (pinfunction "-IN_2") (pintype "input"))
      (node (ref "R12") (pin "1") (pinfunction "1_1") (pintype "passive"))
      (node (ref "R3") (pin "1") (pinfunction "1_1") (pintype "passive"))
    )
    (net (code "70") (name "Net-(IC1B-+IN)") (class "Default")
      (node (ref "IC1") (pin "5") (pinfunction "+IN_5") (pintype "input"))
      (node (ref "R65") (pin "2") (pinfunction "2_2") (pintype "passive"))
    )
    (net (code "71") (name "Net-(IC1B--IN)") (class "Default")
      (node (ref "IC1") (pin "6") (pinfunction "-IN_6") (pintype "input"))
      (node (ref "IC1") (pin "7") (pinfunction "OUT_7") (pintype "output"))
      (node (ref "R22") (pin "1") (pinfunction "1_1") (pintype "passive"))
      (node (ref "R31") (pin "1") (pinfunction "1_1") (pintype "passive"))
    )
    (net (code "72") (name "Net-(IC1C--IN)") (class "Default")
      (node (ref "IC1") (pin "9") (pinfunction "-IN_9") (pintype "input"))
      (node (ref "R3") (pin "2") (pinfunction "2_2") (pintype "passive"))
      (node (ref "R4") (pin "1") (pinfunction "1_1") (pintype "passive"))
      (node (ref "R53") (pin "2") (pinfunction "2_2") (pintype "passive"))
      (node (ref "R8") (pin "1") (pinfunction "1_1") (pintype "passive"))
    )
    (net (code "73") (name "Net-(IC1D--IN)") (class "Default")
      (node (ref "IC1") (pin "13") (pinfunction "-IN_13") (pintype "input"))
      (node (ref "R14") (pin "1") (pinfunction "1_1") (pintype "passive"))
      (node (ref "R21") (pin "1") (pinfunction "1_1") (pintype "passive"))
      (node (ref "R31") (pin "2") (pinfunction "2_2") (pintype "passive"))
    )
    (net (code "74") (name "Net-(IC2A-IN)") (class "Default")
      (node (ref "IC2") (pin "2") (pinfunction "IN_2") (pintype "input"))
      (node (ref "R34") (pin "2") (pinfunction "2_2") (pintype "passive"))
      (node (ref "R35") (pin "2") (pinfunction "2_2") (pintype "passive"))
    )
    (net (code "75") (name "Net-(IC2B-IN)") (class "Default")
      (node (ref "IC2") (pin "7") (pinfunction "IN_7") (pintype "input"))
      (node (ref "R5") (pin "2") (pinfunction "2_2") (pintype "passive"))
      (node (ref "R6") (pin "2") (pinfunction "2_2") (pintype "passive"))
    )
    (net (code "76") (name "Net-(IC2B-OUT)") (class "Default")
      (node (ref "C4") (pin "2") (pinfunction "2_2") (pintype "passive"))
      (node (ref "IC2") (pin "5") (pinfunction "OUT_5") (pintype "output"))
      (node (ref "IC5") (pin "6") (pinfunction "-IN_6") (pintype "input"))
      (node (ref "R10") (pin "1") (pinfunction "1_1") (pintype "passive"))
    )
    (net (code "77") (name "Net-(IC2C-IN)") (class "Default")
      (node (ref "IC2") (pin "10") (pinfunction "IN_10") (pintype "input"))
      (node (ref "R11") (pin "2") (pinfunction "2_2") (pintype "passive"))
      (node (ref "R7") (pin "2") (pinfunction "2_2") (pintype "passive"))
    )
    (net (code "78") (name "Net-(IC2C-OUT)") (class "Default")
      (node (ref "C12") (pin "2") (pinfunction "2_2") (pintype "passive"))
      (node (ref "IC2") (pin "12") (pinfunction "OUT_12") (pintype "output"))
      (node (ref "IC5") (pin "9") (pinfunction "-IN_9") (pintype "input"))
      (node (ref "R36") (pin "1") (pinfunction "1_1") (pintype "passive"))
    )
    (net (code "79") (name "Net-(IC2D-IN)") (class "Default")
      (node (ref "IC2") (pin "15") (pinfunction "IN_15") (pintype "input"))
      (node (ref "R59") (pin "2") (pinfunction "2_2") (pintype "passive"))
      (node (ref "R60") (pin "2") (pinfunction "2_2") (pintype "passive"))
    )
    (net (code "80") (name "Net-(IC2D-OUT)") (class "Default")
      (node (ref "C6") (pin "2") (pinfunction "2_2") (pintype "passive"))
      (node (ref "IC2") (pin "13") (pinfunction "OUT_13") (pintype "output"))
      (node (ref "IC7") (pin "13") (pinfunction "-IN_13") (pintype "input"))
      (node (ref "R58") (pin "1") (pinfunction "1_1") (pintype "passive"))
    )
    (net (code "81") (name "Net-(IC2E-MODE)") (class "Default")
      (node (ref "IC2") (pin "1") (pinfunction "MODE_1") (pintype "input"))
      (node (ref "R94") (pin "1") (pinfunction "1_1") (pintype "passive"))
    )
    (net (code "82") (name "Net-(IC3C-+IN)") (class "Default")
      (node (ref "IC3") (pin "10") (pinfunction "+IN_10") (pintype "input"))
      (node (ref "R97") (pin "2") (pinfunction "2_2") (pintype "passive"))
      (node (ref "R98") (pin "2") (pinfunction "2_2") (pintype "passive"))
    )
    (net (code "83") (name "Net-(IC3C--IN)") (class "Default")
      (node (ref "IC3") (pin "9") (pinfunction "-IN_9") (pintype "input"))
      (node (ref "R95") (pin "1") (pinfunction "1_1") (pintype "passive"))
      (node (ref "R96") (pin "2") (pinfunction "2_2") (pintype "passive"))
    )
    (net (code "84") (name "Net-(IC3D-+IN)") (class "Default")
      (node (ref "IC3") (pin "12") (pinfunction "+IN_12") (pintype "input"))
      (node (ref "R103") (pin "2") (pinfunction "2_2") (pintype "passive"))
      (node (ref "R104") (pin "2") (pinfunction "2_2") (pintype "passive"))
    )
    (net (code "85") (name "Net-(IC3D--IN)") (class "Default")
      (node (ref "IC3") (pin "13") (pinfunction "-IN_13") (pintype "input"))
      (node (ref "R105") (pin "1") (pinfunction "1_1") (pintype "passive"))
      (node (ref "R109") (pin "2") (pinfunction "2_2") (pintype "passive"))
    )
    (net (code "86") (name "Net-(IC4B--IN)") (class "Default")
      (node (ref "IC4") (pin "6") (pinfunction "-IN_6") (pintype "input"))
      (node (ref "IC4") (pin "7") (pinfunction "OUT_7") (pintype "output"))
    )
    (net (code "87") (name "Net-(IC5B-OUT)") (class "Default")
      (node (ref "C4") (pin "1") (pinfunction "1_1") (pintype "passive"))
      (node (ref "IC5") (pin "7") (pinfunction "OUT_7") (pintype "output"))
      (node (ref "R10") (pin "2") (pinfunction "2_2") (pintype "passive"))
      (node (ref "R20") (pin "1") (pinfunction "1_1") (pintype "passive"))
    )
    (net (code "88") (name "Net-(IC5C-OUT)") (class "Default")
      (node (ref "C12") (pin "1") (pinfunction "1_1") (pintype "passive"))
      (node (ref "IC5") (pin "8") (pinfunction "OUT_8") (pintype "output"))
      (node (ref "R29") (pin "1") (pinfunction "1_1") (pintype "passive"))
      (node (ref "R36") (pin "2") (pinfunction "2_2") (pintype "passive"))
    )
    (net (code "89") (name "Net-(IC5D--IN)") (class "Default")
      (node (ref "IC5") (pin "13") (pinfunction "-IN_13") (pintype "input"))
      (node (ref "R115") (pin "1") (pinfunction "1_1") (pintype "passive"))
      (node (ref "R28") (pin "1") (pinfunction "1_1") (pintype "passive"))
      (node (ref "R29") (pin "2") (pinfunction "2_2") (pintype "passive"))
    )
    (net (code "90") (name "Net-(IC5D-OUT)") (class "Default")
      (node (ref "1K") (pin "1") (pinfunction "1_1") (pintype "passive"))
      (node (ref "IC5") (pin "14") (pinfunction "OUT_14") (pintype "output"))
      (node (ref "R28") (pin "2") (pinfunction "2_2") (pintype "passive"))
    )
    (net (code "91") (name "Net-(IC6A-IN)") (class "Default")
      (node (ref "IC6") (pin "2") (pinfunction "IN_2") (pintype "input"))
      (node (ref "R89") (pin "2") (pinfunction "2_2") (pintype "passive"))
      (node (ref "R90") (pin "2") (pinfunction "2_2") (pintype "passive"))
    )
    (net (code "92") (name "Net-(IC6B-IN)") (class "Default")
      (node (ref "IC6") (pin "7") (pinfunction "IN_7") (pintype "input"))
      (node (ref "R54") (pin "2") (pinfunction "2_2") (pintype "passive"))
      (node (ref "R56") (pin "2") (pinfunction "2_2") (pintype "passive"))
    )
    (net (code "93") (name "Net-(IC6B-OUT)") (class "Default")
      (node (ref "C16") (pin "2") (pinfunction "2_2") (pintype "passive"))
      (node (ref "IC6") (pin "5") (pinfunction "OUT_5") (pintype "output"))
      (node (ref "IC8") (pin "6") (pinfunction "-IN_6") (pintype "input"))
      (node (ref "R64") (pin "1") (pinfunction "1_1") (pintype "passive"))
    )
    (net (code "94") (name "Net-(IC6C-IN)") (class "Default")
      (node (ref "IC6") (pin "10") (pinfunction "IN_10") (pintype "input"))
      (node (ref "R45") (pin "2") (pinfunction "2_2") (pintype "passive"))
      (node (ref "R47") (pin "2") (pinfunction "2_2") (pintype "passive"))
    )
    (net (code "95") (name "Net-(IC6C-OUT)") (class "Default")
      (node (ref "C14") (pin "2") (pinfunction "2_2") (pintype "passive"))
      (node (ref "IC6") (pin "12") (pinfunction "OUT_12") (pintype "output"))
      (node (ref "IC8") (pin "9") (pinfunction "-IN_9") (pintype "input"))
      (node (ref "R49") (pin "1") (pinfunction "1_1") (pintype "passive"))
    )
    (net (code "96") (name "Net-(IC6D-IN)") (class "Default")
      (node (ref "IC6") (pin "15") (pinfunction "IN_15") (pintype "input"))
      (node (ref "R84") (pin "2") (pinfunction "2_2") (pintype "passive"))
      (node (ref "R85") (pin "2") (pinfunction "2_2") (pintype "passive"))
    )
    (net (code "97") (name "Net-(IC6E-MODE)") (class "Default")
      (node (ref "IC6") (pin "1") (pinfunction "MODE_1") (pintype "input"))
      (node (ref "R110") (pin "1") (pinfunction "1_1") (pintype "passive"))
    )
    (net (code "98") (name "Net-(IC7A-+IN)") (class "Default")
      (node (ref "IC7") (pin "3") (pinfunction "+IN_3") (pintype "input"))
      (node (ref "R32") (pin "2") (pinfunction "2_2") (pintype "passive"))
    )
    (net (code "99") (name "Net-(IC7A--IN)") (class "Default")
      (node (ref "IC7") (pin "1") (pinfunction "OUT_1") (pintype "output"))
      (node (ref "IC7") (pin "2") (pinfunction "-IN_2") (pintype "input"))
      (node (ref "R33") (pin "2") (pinfunction "2_2") (pintype "passive"))
    )
    (net (code "100") (name "Net-(IC7B--IN)") (class "Default")
      (node (ref "IC7") (pin "6") (pinfunction "-IN_6") (pintype "input"))
      (node (ref "R18") (pin "1") (pinfunction "1_1") (pintype "passive"))
      (node (ref "R55") (pin "2") (pinfunction "2_2") (pintype "passive"))
    )
    (net (code "101") (name "Net-(IC7B-OUT)") (class "Default")
      (node (ref "IC7") (pin "7") (pinfunction "OUT_7") (pintype "output"))
      (node (ref "R18") (pin "2") (pinfunction "2_2") (pintype "passive"))
      (node (ref "R58") (pin "2") (pinfunction "2_2") (pintype "passive"))
    )
    (net (code "102") (name "Net-(IC8B-OUT)") (class "Default")
      (node (ref "C16") (pin "1") (pinfunction "1_1") (pintype "passive"))
      (node (ref "IC8") (pin "7") (pinfunction "OUT_7") (pintype "output"))
      (node (ref "R64") (pin "2") (pinfunction "2_2") (pintype "passive"))
      (node (ref "R66") (pin "1") (pinfunction "1_1") (pintype "passive"))
    )
    (net (code "103") (name "Net-(IC8C-OUT)") (class "Default")
      (node (ref "C14") (pin "1") (pinfunction "1_1") (pintype "passive"))
      (node (ref "IC8") (pin "8") (pinfunction "OUT_8") (pintype "output"))
      (node (ref "R49") (pin "2") (pinfunction "2_2") (pintype "passive"))
      (node (ref "R68") (pin "1") (pinfunction "1_1") (pintype "passive"))
    )
    (net (code "104") (name "Net-(IC8D--IN)") (class "Default")
      (node (ref "IC8") (pin "13") (pinfunction "-IN_13") (pintype "input"))
      (node (ref "R116") (pin "1") (pinfunction "1_1") (pintype "passive"))
      (node (ref "R67") (pin "1") (pinfunction "1_1") (pintype "passive"))
      (node (ref "R68") (pin "2") (pinfunction "2_2") (pintype "passive"))
    )
    (net (code "105") (name "Net-(IC8D-OUT)") (class "Default")
      (node (ref "1K1") (pin "1") (pinfunction "1_1") (pintype "passive"))
      (node (ref "IC8") (pin "14") (pinfunction "OUT_14") (pintype "output"))
      (node (ref "R67") (pin "2") (pinfunction "2_2") (pintype "passive"))
    )
    (net (code "106") (name "Net-(IC9A-+IN)") (class "Default")
      (node (ref "IC9") (pin "3") (pinfunction "+IN_3") (pintype "input"))
      (node (ref "R72") (pin "2") (pinfunction "2_2") (pintype "passive"))
    )
    (net (code "107") (name "Net-(IC9A--IN)") (class "Default")
      (node (ref "IC9") (pin "1") (pinfunction "OUT_1") (pintype "output"))
      (node (ref "IC9") (pin "2") (pinfunction "-IN_2") (pintype "input"))
      (node (ref "R78") (pin "1") (pinfunction "1_1") (pintype "passive"))
      (node (ref "R80") (pin "1") (pinfunction "1_1") (pintype "passive"))
    )
    (net (code "108") (name "Net-(IC9B-+IN)") (class "Default")
      (node (ref "IC9") (pin "5") (pinfunction "+IN_5") (pintype "input"))
      (node (ref "R74") (pin "2") (pinfunction "2_2") (pintype "passive"))
    )
    (net (code "109") (name "Net-(IC9B--IN)") (class "Default")
      (node (ref "IC9") (pin "6") (pinfunction "-IN_6") (pintype "input"))
      (node (ref "IC9") (pin "7") (pinfunction "OUT_7") (pintype "output"))
      (node (ref "R75") (pin "1") (pinfunction "1_1") (pintype "passive"))
      (node (ref "R77") (pin "1") (pinfunction "1_1") (pintype "passive"))
    )
    (net (code "110") (name "Net-(IC9C--IN)") (class "Default")
      (node (ref "IC9") (pin "9") (pinfunction "-IN_9") (pintype "input"))
      (node (ref "R73") (pin "2") (pinfunction "2_2") (pintype "passive"))
      (node (ref "R78") (pin "2") (pinfunction "2_2") (pintype "passive"))
      (node (ref "R79") (pin "1") (pinfunction "1_1") (pintype "passive"))
      (node (ref "R81") (pin "1") (pinfunction "1_1") (pintype "passive"))
    )
    (net (code "111") (name "Net-(IC9D--IN)") (class "Default")
      (node (ref "IC9") (pin "13") (pinfunction "-IN_13") (pintype "input"))
      (node (ref "R75") (pin "2") (pinfunction "2_2") (pintype "passive"))
      (node (ref "R76") (pin "1") (pinfunction "1_1") (pintype "passive"))
      (node (ref "R82") (pin "1") (pinfunction "1_1") (pintype "passive"))
    )
    (net (code "112") (name "Net-(IC10A-+IN)") (class "Default")
      (node (ref "IC10") (pin "3") (pinfunction "+IN_3") (pintype "input"))
      (node (ref "R16") (pin "2") (pinfunction "2_2") (pintype "passive"))
    )
    (net (code "113") (name "Net-(IC10A--IN)") (class "Default")
      (node (ref "IC10") (pin "1") (pinfunction "OUT_1") (pintype "output"))
      (node (ref "IC10") (pin "2") (pinfunction "-IN_2") (pintype "input"))
      (node (ref "R83") (pin "2") (pinfunction "2_2") (pintype "passive"))
    )
    (net (code "114") (name "Net-(IC10B--IN)") (class "Default")
      (node (ref "IC10") (pin "6") (pinfunction "-IN_6") (pintype "input"))
      (node (ref "R87") (pin "2") (pinfunction "2_2") (pintype "passive"))
      (node (ref "R92") (pin "1") (pinfunction "1_1") (pintype "passive"))
    )
    (net (code "115") (name "Net-(IC10B-OUT)") (class "Default")
      (node (ref "IC10") (pin "7") (pinfunction "OUT_7") (pintype "output"))
      (node (ref "R88") (pin "2") (pinfunction "2_2") (pintype "passive"))
      (node (ref "R92") (pin "2") (pinfunction "2_2") (pintype "passive"))
    )
    (net (code "116") (name "Net-(IC11A-+IN)") (class "Default")
      (node (ref "C1") (pin "1") (pinfunction "1_1") (pintype "passive"))
      (node (ref "IC11") (pin "3") (pinfunction "+IN_3") (pintype "input"))
      (node (ref "OFFSET_LINA") (pin "2") (pinfunction "S_2") (pintype "passive"))
    )
    (net (code "117") (name "Net-(IC11B-+IN)") (class "Default")
      (node (ref "C20") (pin "1") (pinfunction "1_1") (pintype "passive"))
      (node (ref "IC11") (pin "5") (pinfunction "+IN_5") (pintype "input"))
      (node (ref "OFFSET_LINB") (pin "2") (pinfunction "S_2") (pintype "passive"))
    )
    (net (code "118") (name "Net-(IC12A--IN)") (class "Default")
      (node (ref "IC12") (pin "2") (pinfunction "-IN_2") (pintype "input"))
      (node (ref "R100") (pin "2") (pinfunction "2_2") (pintype "passive"))
      (node (ref "R101") (pin "1") (pinfunction "1_1") (pintype "passive"))
    )
    (net (code "119") (name "Net-(IC12A-OUT)") (class "Default")
      (node (ref "IC12") (pin "1") (pinfunction "OUT_1") (pintype "output"))
      (node (ref "R100") (pin "1") (pinfunction "1_1") (pintype "passive"))
      (node (ref "R102") (pin "2") (pinfunction "2_2") (pintype "passive"))
    )
    (net (code "120") (name "Net-(IC12B--IN)") (class "Default")
      (node (ref "IC12") (pin "6") (pinfunction "-IN_6") (pintype "input"))
      (node (ref "R102") (pin "1") (pinfunction "1_1") (pintype "passive"))
      (node (ref "R99") (pin "2") (pinfunction "2_2") (pintype "passive"))
    )
    (net (code "121") (name "Net-(IC12B-OUT)") (class "Default")
      (node (ref "IC12") (pin "7") (pinfunction "OUT_7") (pintype "output"))
      (node (ref "R97") (pin "1") (pinfunction "1_1") (pintype "passive"))
      (node (ref "R99") (pin "1") (pinfunction "1_1") (pintype "passive"))
    )
    (net (code "122") (name "Net-(IC12C--IN)") (class "Default")
      (node (ref "IC12") (pin "9") (pinfunction "-IN_9") (pintype "input"))
      (node (ref "R107") (pin "1") (pinfunction "1_1") (pintype "passive"))
      (node (ref "R108") (pin "2") (pinfunction "2_2") (pintype "passive"))
    )
    (net (code "123") (name "Net-(IC12C-OUT)") (class "Default")
      (node (ref "IC12") (pin "8") (pinfunction "OUT_8") (pintype "output"))
      (node (ref "R103") (pin "1") (pinfunction "1_1") (pintype "passive"))
      (node (ref "R108") (pin "1") (pinfunction "1_1") (pintype "passive"))
    )
    (net (code "124") (name "Net-(IC12D-+IN)") (class "Default")
      (node (ref "C24") (pin "1") (pinfunction "1_1") (pintype "passive"))
      (node (ref "IC12") (pin "12") (pinfunction "+IN_12") (pintype "input"))
      (node (ref "OFFSET_REFB") (pin "2") (pinfunction "S_2") (pintype "passive"))
    )
    (net (code "125") (name "Net-(IC14A--IN)") (class "Default")
      (node (ref "IC14") (pin "2") (pinfunction "-IN_2") (pintype "input"))
      (node (ref "R39") (pin "2") (pinfunction "2_2") (pintype "passive"))
      (node (ref "R42") (pin "1") (pinfunction "1_1") (pintype "passive"))
    )
    (net (code "126") (name "Net-(IC14A-OUT)") (class "Default")
      (node (ref "IC14") (pin "1") (pinfunction "OUT_1") (pintype "output"))
      (node (ref "R15") (pin "2") (pinfunction "2_2") (pintype "passive"))
      (node (ref "R39") (pin "1") (pinfunction "1_1") (pintype "passive"))
    )
    (net (code "127") (name "Net-(IC14B-+IN)") (class "Default")
      (node (ref "IC14") (pin "5") (pinfunction "+IN_5") (pintype "input"))
      (node (ref "R17") (pin "1") (pinfunction "1_1") (pintype "passive"))
      (node (ref "R25") (pin "2") (pinfunction "2_2") (pintype "passive"))
    )
    (net (code "128") (name "Net-(IC14B--IN)") (class "Default")
      (node (ref "IC14") (pin "6") (pinfunction "-IN_6") (pintype "input"))
      (node (ref "R131") (pin "1") (pinfunction "1_1") (pintype "passive"))
      (node (ref "R15") (pin "1") (pinfunction "1_1") (pintype "passive"))
      (node (ref "R38") (pin "2") (pinfunction "2_2") (pintype "passive"))
    )
    (net (code "129") (name "Net-(IC14C-+IN)") (class "Default")
      (node (ref "IC14") (pin "10") (pinfunction "+IN_10") (pintype "input"))
      (node (ref "R23") (pin "2") (pinfunction "2_2") (pintype "passive"))
      (node (ref "R46") (pin "2") (pinfunction "2_2") (pintype "passive"))
    )
    (net (code "130") (name "Net-(IC14C--IN)") (class "Default")
      (node (ref "IC14") (pin "9") (pinfunction "-IN_9") (pintype "input"))
      (node (ref "R19") (pin "2") (pinfunction "2_2") (pintype "passive"))
      (node (ref "R40") (pin "1") (pinfunction "1_1") (pintype "passive"))
      (node (ref "R41") (pin "2") (pinfunction "2_2") (pintype "passive"))
    )
    (net (code "131") (name "Net-(IC14D--IN)") (class "Default")
      (node (ref "IC14") (pin "13") (pinfunction "-IN_13") (pintype "input"))
      (node (ref "R129") (pin "1") (pinfunction "1_1") (pintype "passive"))
      (node (ref "R130") (pin "1") (pinfunction "1_1") (pintype "passive"))
    )
    (net (code "132") (name "Net-(OFFSET_LINA-E)") (class "Default")
      (node (ref "OFFSET_LINA") (pin "3") (pinfunction "E_3") (pintype "passive"))
      (node (ref "R13") (pin "1") (pinfunction "1_1") (pintype "passive"))
    )
    (net (code "133") (name "Net-(OFFSET_LINB-E)") (class "Default")
      (node (ref "OFFSET_LINB") (pin "3") (pinfunction "E_3") (pintype "passive"))
      (node (ref "R93") (pin "1") (pinfunction "1_1") (pintype "passive"))
    )
    (net (code "134") (name "Net-(OFFSET_REF-E)") (class "Default")
      (node (ref "OFFSET_REF") (pin "3") (pinfunction "E_3") (pintype "passive"))
      (node (ref "R2") (pin "1") (pinfunction "1_1") (pintype "passive"))
    )
    (net (code "135") (name "Net-(OFFSET_REF-S)") (class "Default")
      (node (ref "C9") (pin "1") (pinfunction "1_1") (pintype "passive"))
      (node (ref "OFFSET_REF") (pin "2") (pinfunction "S_2") (pintype "passive"))
      (node (ref "R129") (pin "2") (pinfunction "2_2") (pintype "passive"))
    )
    (net (code "136") (name "Net-(OFFSET_REFB-E)") (class "Default")
      (node (ref "OFFSET_REFB") (pin "3") (pinfunction "E_3") (pintype "passive"))
      (node (ref "R106") (pin "1") (pinfunction "1_1") (pintype "passive"))
    )
    (net (code "137") (name "Net-(Q1-PadB)") (class "Default")
      (node (ref "Q1") (pin "B") (pinfunction "B_B") (pintype "passive"))
      (node (ref "R113") (pin "2") (pinfunction "2_2") (pintype "passive"))
      (node (ref "R115") (pin "2") (pinfunction "2_2") (pintype "passive"))
    )
    (net (code "138") (name "Net-(Q2-PadB)") (class "Default")
      (node (ref "Q2") (pin "B") (pinfunction "B_B") (pintype "passive"))
      (node (ref "R123") (pin "2") (pinfunction "2_2") (pintype "passive"))
      (node (ref "R125") (pin "2") (pinfunction "2_2") (pintype "passive"))
    )
    (net (code "139") (name "Net-(Q3-PadB)") (class "Default")
      (node (ref "Q3") (pin "B") (pinfunction "B_B") (pintype "passive"))
      (node (ref "R126") (pin "2") (pinfunction "2_2") (pintype "passive"))
      (node (ref "R128") (pin "2") (pinfunction "2_2") (pintype "passive"))
    )
    (net (code "140") (name "Net-(Q5-PadB)") (class "Default")
      (node (ref "Q5") (pin "B") (pinfunction "B_B") (pintype "passive"))
      (node (ref "R111") (pin "2") (pinfunction "2_2") (pintype "passive"))
      (node (ref "R116") (pin "2") (pinfunction "2_2") (pintype "passive"))
    )
    (net (code "141") (name "Net-(Q9-D)") (class "Default")
      (node (ref "JP8") (pin "1") (pinfunction "1_1") (pintype "passive"))
      (node (ref "JP8") (pin "2") (pinfunction "2_2") (pintype "passive"))
      (node (ref "Q9") (pin "3") (pinfunction "D_3") (pintype "passive"))
    )
    (net (code "142") (name "Net-(Q10-D)") (class "Default")
      (node (ref "JP8") (pin "10") (pinfunction "10_10") (pintype "passive"))
      (node (ref "JP8") (pin "9") (pinfunction "9_9") (pintype "passive"))
      (node (ref "Q10") (pin "3") (pinfunction "D_3") (pintype "passive"))
    )
    (net (code "143") (name "Net-(R5-Pad1)") (class "Default")
      (node (ref "R5") (pin "1") (pinfunction "1_1") (pintype "passive"))
      (node (ref "R9") (pin "2") (pinfunction "2_2") (pintype "passive"))
    )
    (net (code "144") (name "Net-(R24-Pad2)") (class "Default")
      (node (ref "R24") (pin "2") (pinfunction "2_2") (pintype "passive"))
      (node (ref "R7") (pin "1") (pinfunction "1_1") (pintype "passive"))
    )
    (net (code "145") (name "Net-(R45-Pad1)") (class "Default")
      (node (ref "R45") (pin "1") (pinfunction "1_1") (pintype "passive"))
      (node (ref "R48") (pin "2") (pinfunction "2_2") (pintype "passive"))
    )
    (net (code "146") (name "Net-(R54-Pad1)") (class "Default")
      (node (ref "R54") (pin "1") (pinfunction "1_1") (pintype "passive"))
      (node (ref "R57") (pin "2") (pinfunction "2_2") (pintype "passive"))
    )
    (net (code "147") (name "OFFSET_LIN_A") (class "Default")
      (node (ref "IC11") (pin "1") (pinfunction "OUT_1") (pintype "output"))
      (node (ref "IC11") (pin "2") (pinfunction "-IN_2") (pintype "input"))
      (node (ref "IC7") (pin "10") (pinfunction "+IN_10") (pintype "input"))
      (node (ref "IC7") (pin "12") (pinfunction "+IN_12") (pintype "input"))
    )
    (net (code "148") (name "OFFSET_LIN_B") (class "Default")
      (node (ref "IC10") (pin "10") (pinfunction "+IN_10") (pintype "input"))
      (node (ref "IC10") (pin "12") (pinfunction "+IN_12") (pintype "input"))
      (node (ref "IC11") (pin "6") (pinfunction "-IN_6") (pintype "input"))
      (node (ref "IC11") (pin "7") (pinfunction "OUT_7") (pintype "output"))
    )
    (net (code "149") (name "OFFSET_REF") (class "Default")
      (node (ref "IC14") (pin "14") (pinfunction "OUT_14") (pintype "output"))
      (node (ref "R130") (pin "2") (pinfunction "2_2") (pintype "passive"))
      (node (ref "R131") (pin "2") (pinfunction "2_2") (pintype "passive"))
      (node (ref "R19") (pin "1") (pinfunction "1_1") (pintype "passive"))
    )
    (net (code "150") (name "OFFSET_REF_B") (class "Default")
      (node (ref "IC12") (pin "10") (pinfunction "+IN_10") (pintype "input"))
      (node (ref "IC12") (pin "13") (pinfunction "-IN_13") (pintype "input"))
      (node (ref "IC12") (pin "14") (pinfunction "OUT_14") (pintype "output"))
      (node (ref "IC12") (pin "5") (pinfunction "+IN_5") (pintype "input"))
    )
    (net (code "151") (name "OUT_A") (class "Default")
      (node (ref "1K") (pin "2") (pinfunction "2_2") (pintype "passive"))
      (node (ref "J2") (pin "1") (pinfunction "1_1") (pintype "passive"))
      (node (ref "JP7") (pin "7") (pinfunction "7_7") (pintype "passive"))
      (node (ref "OUT_A") (pin "P$3") (pinfunction "3_P$3") (pintype "passive"))
    )
    (net (code "152") (name "OUT_A+") (class "Default")
      (node (ref "JP7") (pin "5") (pinfunction "5_5") (pintype "passive"))
    )
    (net (code "153") (name "OUT_A-") (class "Default")
      (node (ref "JP7") (pin "6") (pinfunction "6_6") (pintype "passive"))
    )
    (net (code "154") (name "OUT_B") (class "Default")
      (node (ref "1K1") (pin "2") (pinfunction "2_2") (pintype "passive"))
      (node (ref "J2") (pin "5") (pinfunction "5_5") (pintype "passive"))
      (node (ref "JP7") (pin "3") (pinfunction "3_3") (pintype "passive"))
      (node (ref "OUT_B") (pin "P$3") (pinfunction "3_P$3") (pintype "passive"))
    )
    (net (code "155") (name "POT_EXPA_1") (class "Default")
      (node (ref "IC1") (pin "12") (pinfunction "+IN_12") (pintype "input"))
      (node (ref "JP2") (pin "4") (pinfunction "4_4") (pintype "passive"))
      (node (ref "JP3") (pin "4") (pinfunction "4_4") (pintype "passive"))
      (node (ref "POT_EXPA") (pin "1") (pinfunction "1_1") (pintype "bidirectional"))
      (node (ref "R22") (pin "2") (pinfunction "2_2") (pintype "passive"))
    )
    (net (code "156") (name "POT_EXPA_3") (class "Default")
      (node (ref "JP2") (pin "3") (pinfunction "3_3") (pintype "passive"))
      (node (ref "JP3") (pin "3") (pinfunction "3_3") (pintype "passive"))
      (node (ref "POT_EXPA") (pin "3") (pinfunction "3_3") (pintype "bidirectional"))
      (node (ref "R14") (pin "2") (pinfunction "2_2") (pintype "passive"))
    )
    (net (code "157") (name "POT_EXPB_1") (class "Default")
      (node (ref "IC9") (pin "12") (pinfunction "+IN_12") (pintype "input"))
      (node (ref "JP2") (pin "2") (pinfunction "2_2") (pintype "passive"))
      (node (ref "JP3") (pin "2") (pinfunction "2_2") (pintype "passive"))
      (node (ref "POT_EXPB") (pin "1") (pinfunction "1_1") (pintype "bidirectional"))
      (node (ref "R77") (pin "2") (pinfunction "2_2") (pintype "passive"))
    )
    (net (code "158") (name "POT_EXPB_3") (class "Default")
      (node (ref "JP2") (pin "1") (pinfunction "1_1") (pintype "passive"))
      (node (ref "JP3") (pin "1") (pinfunction "1_1") (pintype "passive"))
      (node (ref "POT_EXPB") (pin "3") (pinfunction "3_3") (pintype "bidirectional"))
      (node (ref "R82") (pin "2") (pinfunction "2_2") (pintype "passive"))
    )
    (net (code "159") (name "POT_LINA_1") (class "Default")
      (node (ref "IC1") (pin "10") (pinfunction "+IN_10") (pintype "input"))
      (node (ref "JP3") (pin "9") (pinfunction "9_9") (pintype "passive"))
      (node (ref "POT_LINA") (pin "1") (pinfunction "1_1") (pintype "bidirectional"))
      (node (ref "R12") (pin "2") (pinfunction "2_2") (pintype "passive"))
    )
    (net (code "160") (name "POT_LINA_3") (class "Default")
      (node (ref "JP2") (pin "8") (pinfunction "8_8") (pintype "passive"))
      (node (ref "JP3") (pin "8") (pinfunction "8_8") (pintype "passive"))
      (node (ref "POT_LINA") (pin "3") (pinfunction "3_3") (pintype "bidirectional"))
      (node (ref "R8") (pin "2") (pinfunction "2_2") (pintype "passive"))
    )
    (net (code "161") (name "POT_LINB_1") (class "Default")
      (node (ref "IC9") (pin "10") (pinfunction "+IN_10") (pintype "input"))
      (node (ref "JP2") (pin "7") (pinfunction "7_7") (pintype "passive"))
      (node (ref "JP2") (pin "9") (pinfunction "9_9") (pintype "passive"))
      (node (ref "JP3") (pin "7") (pinfunction "7_7") (pintype "passive"))
      (node (ref "POT_LINB") (pin "1") (pinfunction "1_1") (pintype "bidirectional"))
      (node (ref "R80") (pin "2") (pinfunction "2_2") (pintype "passive"))
    )
    (net (code "162") (name "POT_LINB_3") (class "Default")
      (node (ref "JP2") (pin "6") (pinfunction "6_6") (pintype "passive"))
      (node (ref "JP3") (pin "6") (pinfunction "6_6") (pintype "passive"))
      (node (ref "POT_LINB") (pin "3") (pinfunction "3_3") (pintype "bidirectional"))
      (node (ref "R81") (pin "2") (pinfunction "2_2") (pintype "passive"))
    )
    (net (code "163") (name "UNIPOLAR_A") (class "Default")
      (node (ref "JP10") (pin "3") (pinfunction "3_3") (pintype "passive"))
      (node (ref "JP9") (pin "3") (pinfunction "3_3") (pintype "passive"))
      (node (ref "R119") (pin "1") (pinfunction "1_1") (pintype "passive"))
      (node (ref "S1") (pin "3") (pinfunction "S_3") (pintype "passive"))
    )
    (net (code "164") (name "UNIPOLAR_B") (class "Default")
      (node (ref "JP10") (pin "1") (pinfunction "1_1") (pintype "passive"))
      (node (ref "JP9") (pin "1") (pinfunction "1_1") (pintype "passive"))
      (node (ref "R120") (pin "1") (pinfunction "1_1") (pintype "passive"))
      (node (ref "S2") (pin "3") (pinfunction "S_3") (pintype "passive"))
    )
    (net (code "165") (name "unconnected-(S1-O-Pad1)") (class "Default")
      (node (ref "S1") (pin "1") (pinfunction "O_1") (pintype "passive"))
    )
    (net (code "166") (name "unconnected-(S2-O-Pad1)") (class "Default")
      (node (ref "S2") (pin "1") (pinfunction "O_1") (pintype "passive"))
    )
  )
)
